# MotorControlV4_0.net
KiCad netlist of a schematic drawn in Altium Designer
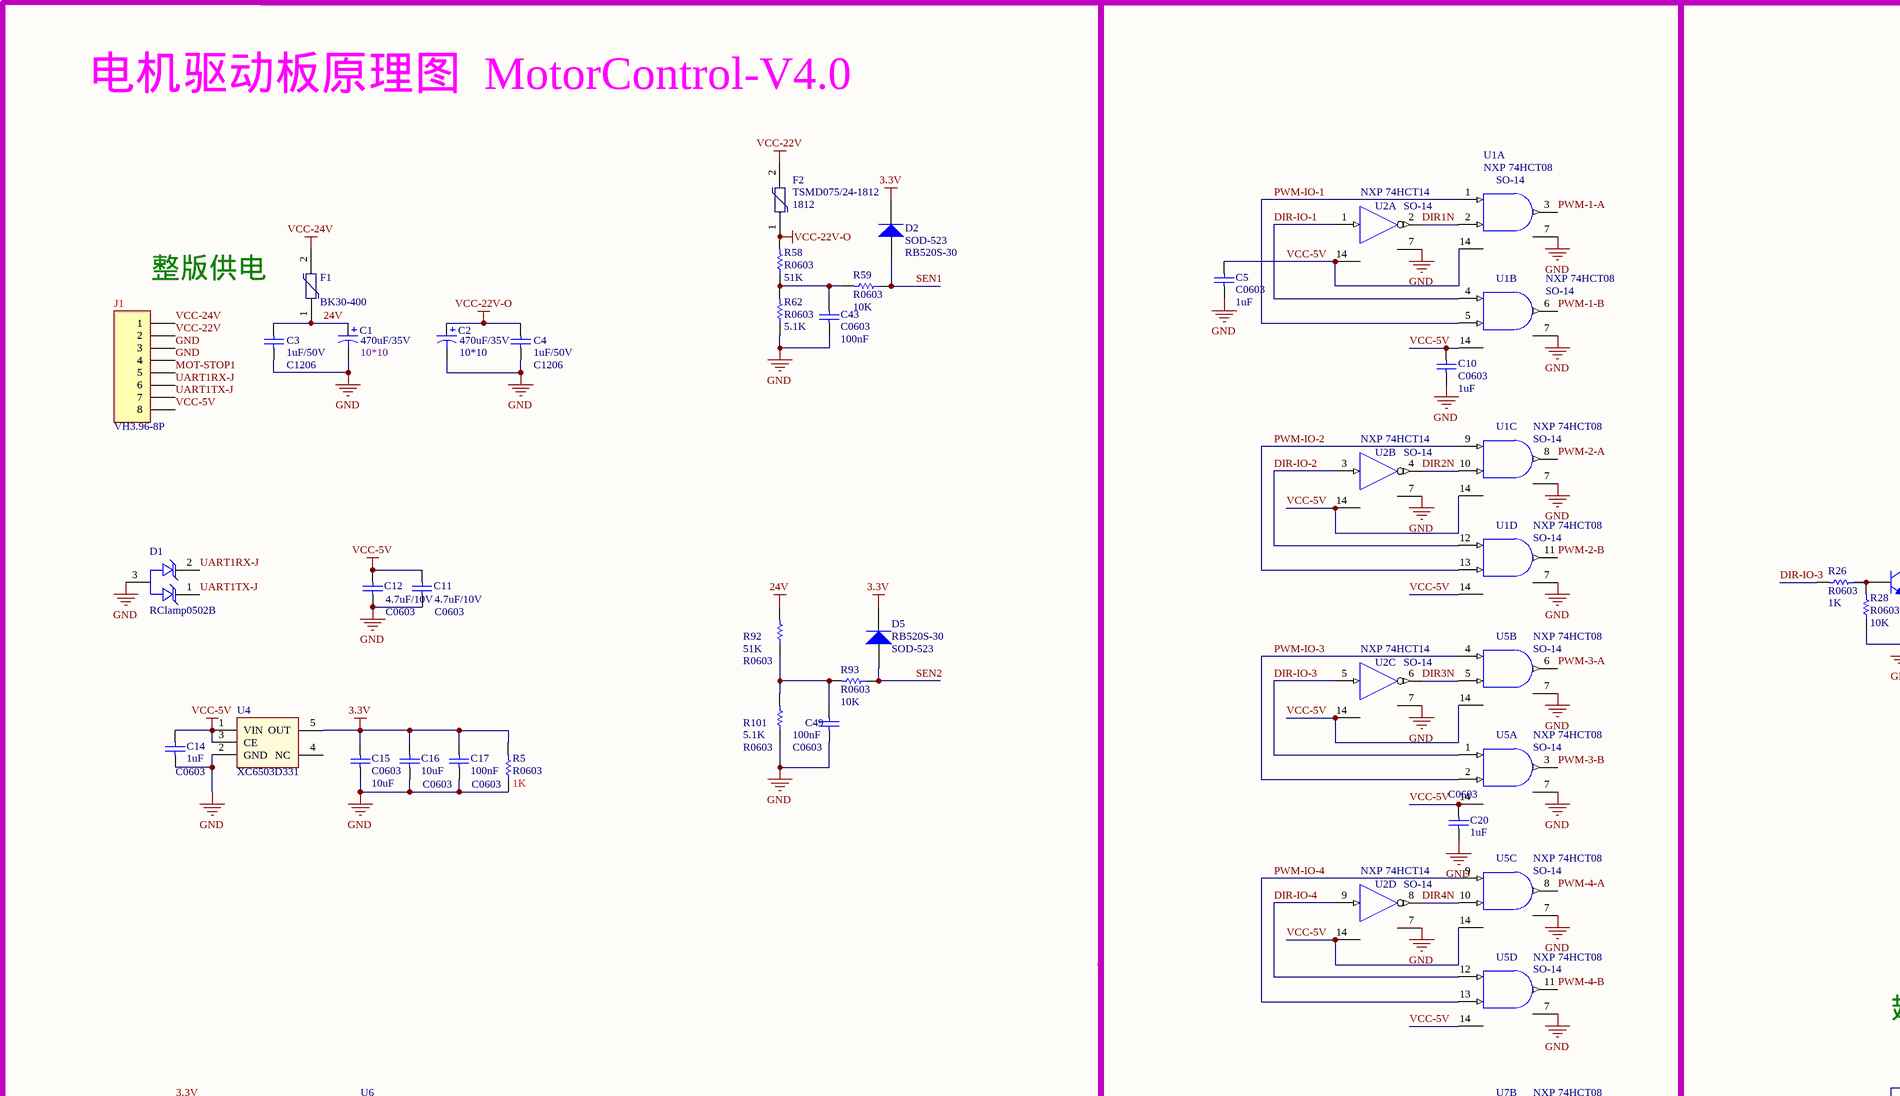
[diagram p0: MotorControlV4.0原理图.SchDoc, top left]
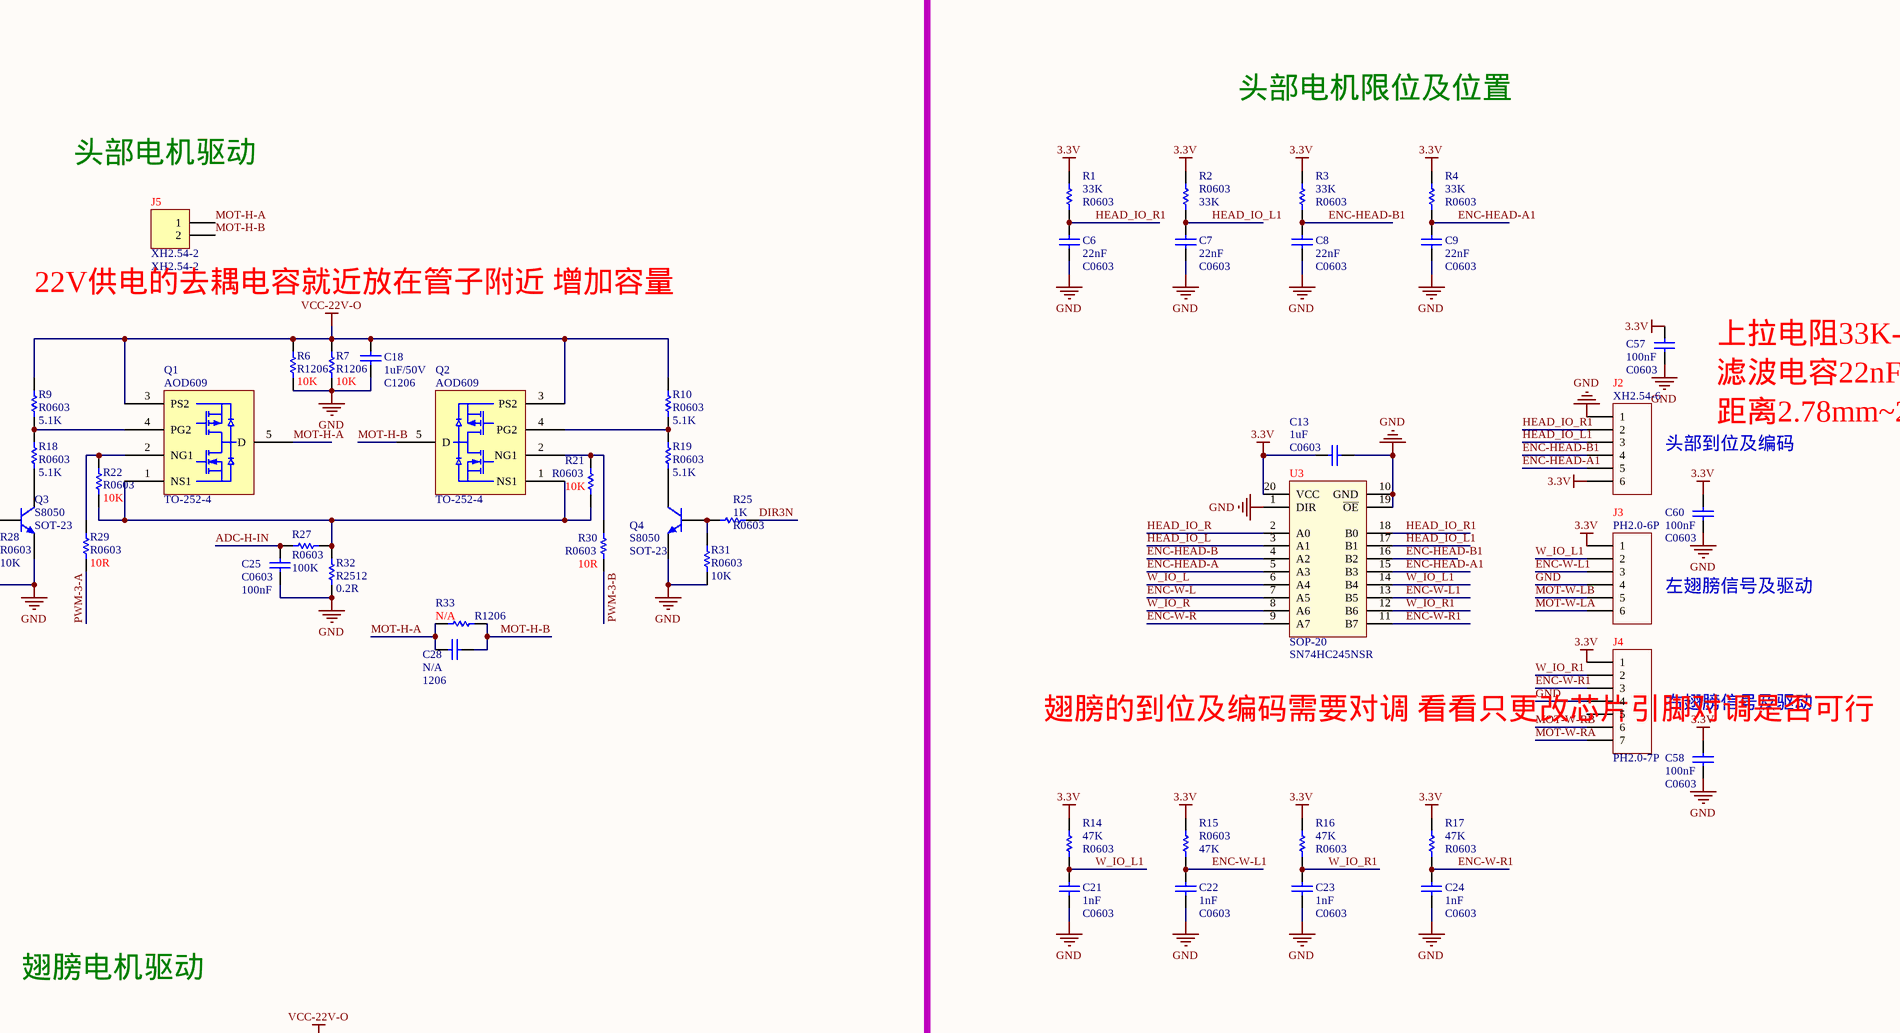
[diagram p1: MotorControlV4.0原理图.SchDoc, top right]
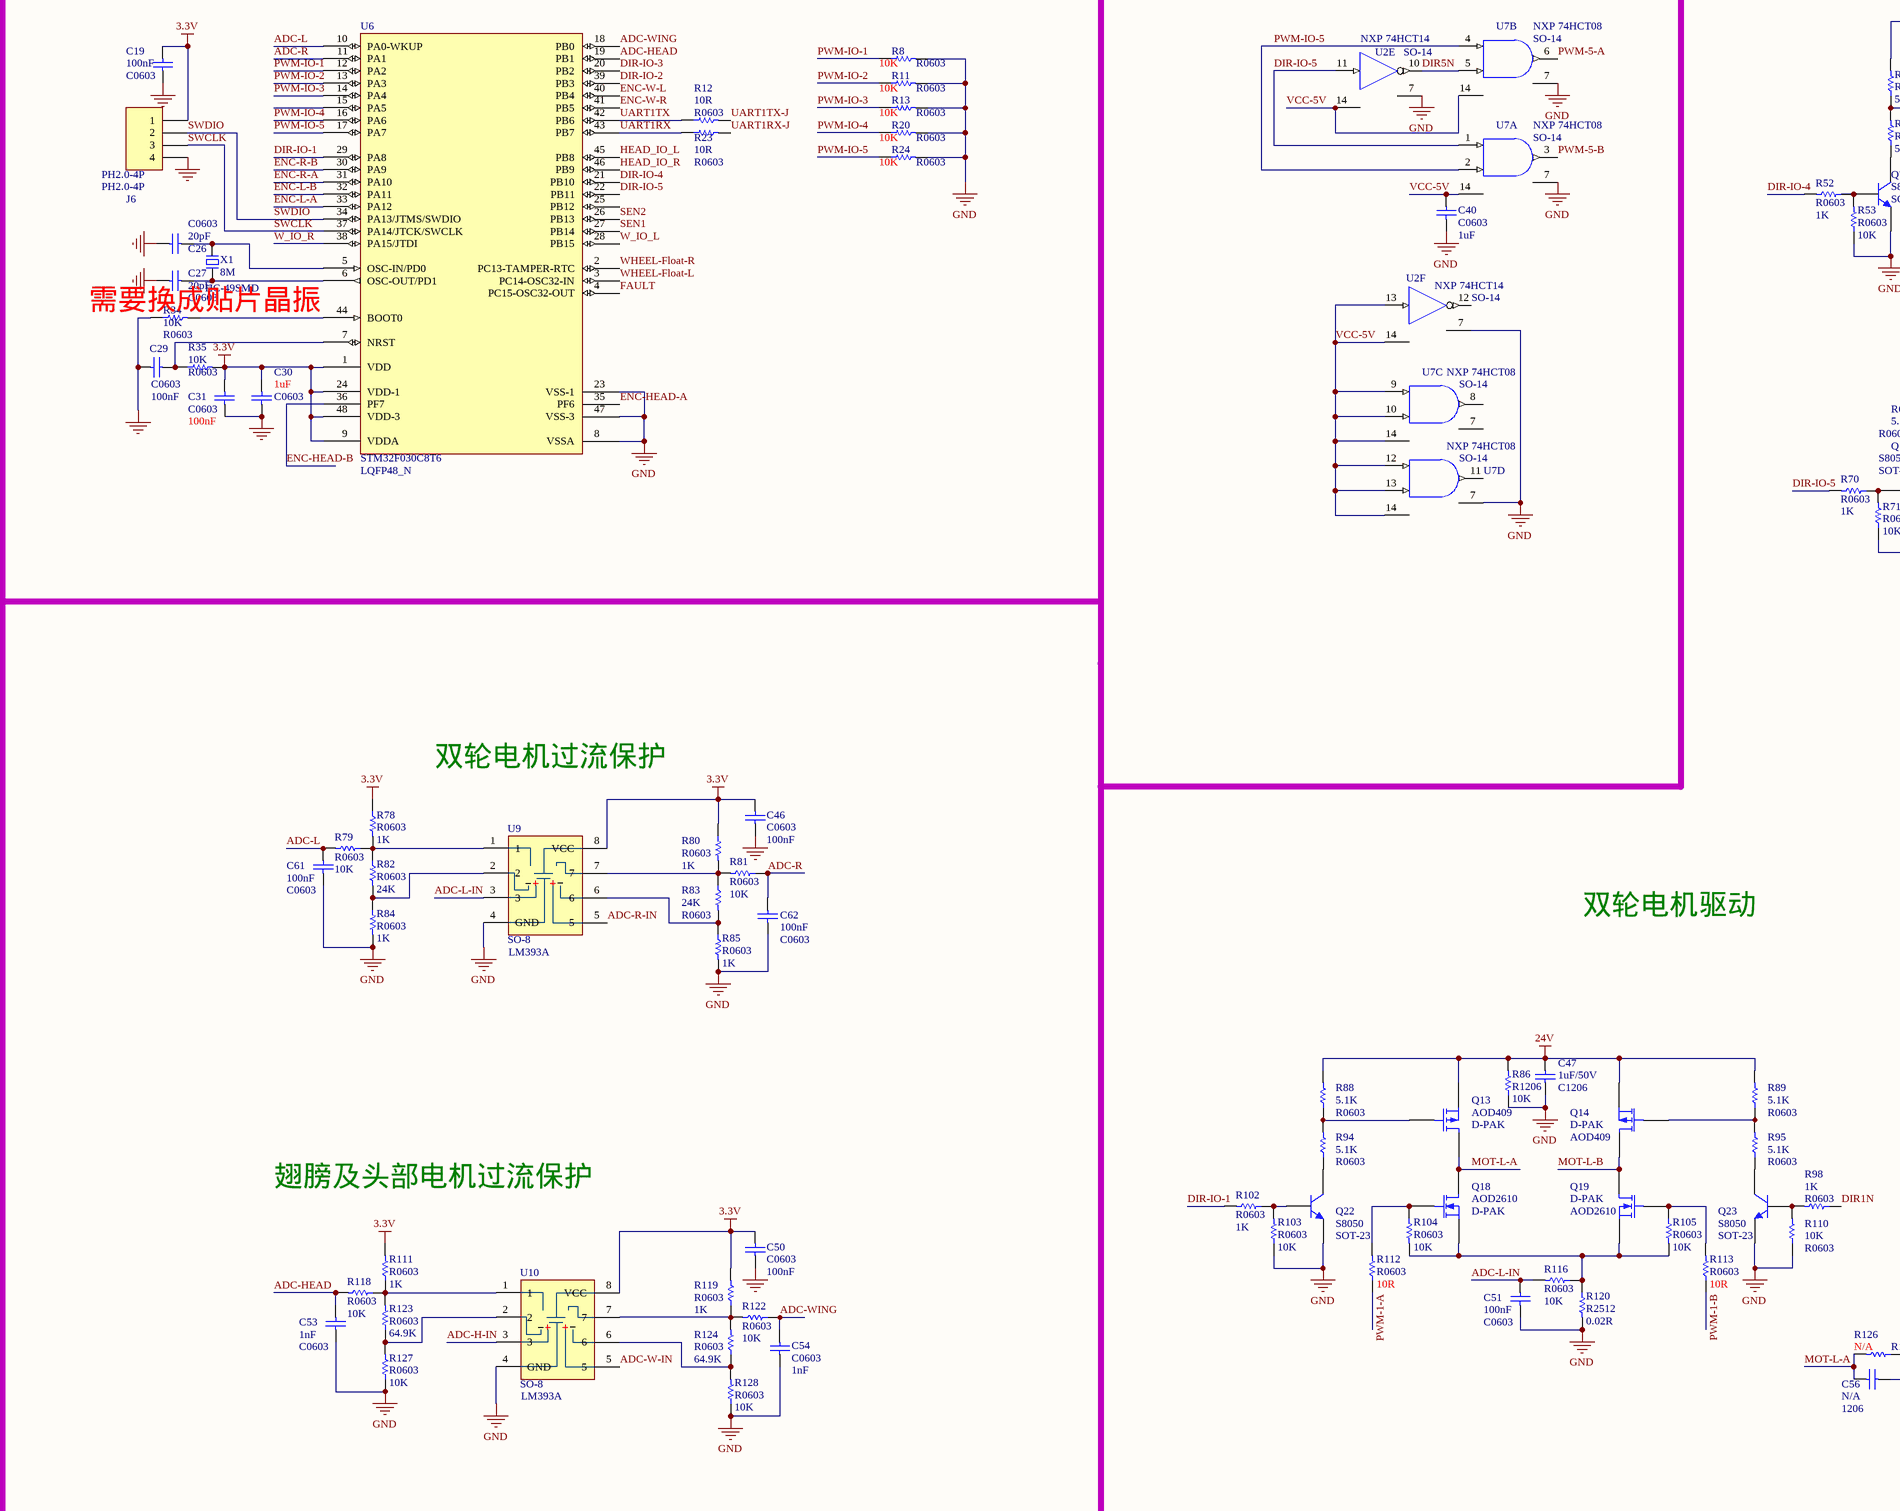
[diagram p2: MotorControlV4.0原理图.SchDoc, bottom left]
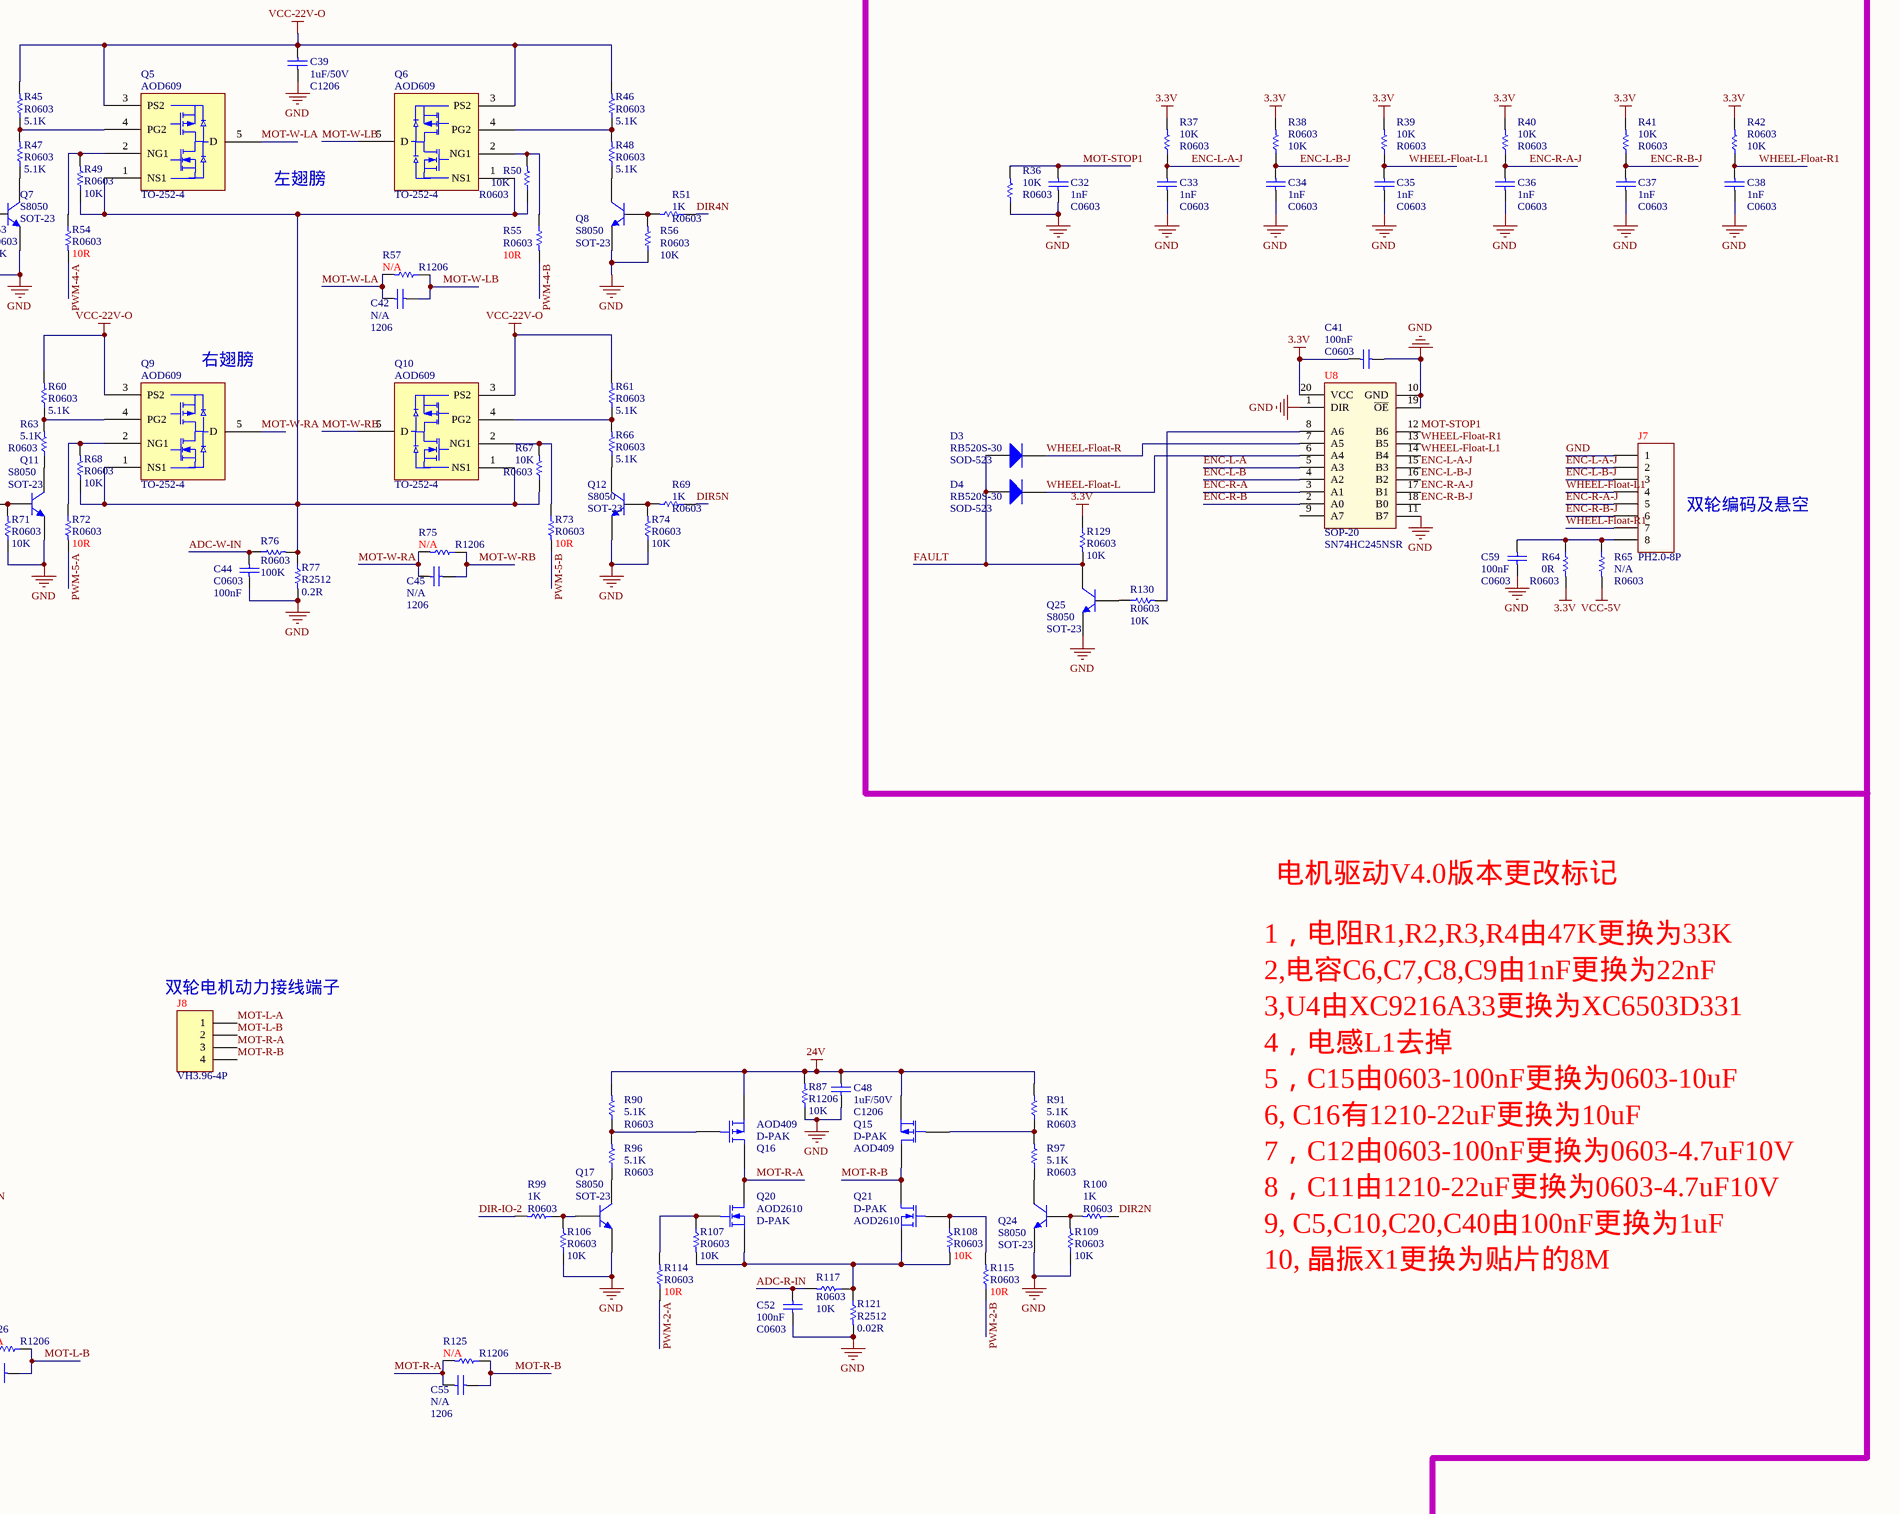
[diagram p3: MotorControlV4.0原理图.SchDoc, bottom right]

(export (version "E")
  (design (tool "Eeschema 10.0.6"))
  (components
    (comp (ref "C1")
      (value "470uF/35V")
      (footprint "CAP_SO_10*10")
      (description "Polarized Capacitor (Surface Mount)")
      (fields (field (name "ALTIUM_VALUE") "10*10") (field (name "PUBLISHER") "Altium Limited"))
      (libsource (lib "Miscellaneous Devices") (part "Cap Pol3"))
    )
    (comp (ref "C2")
      (value "470uF/35V")
      (footprint "CAP_SO_10*10")
      (description "Polarized Capacitor (Surface Mount)")
      (fields (field (name "ALTIUM_VALUE") "10*10") (field (name "PUBLISHER") "Altium Limited"))
      (libsource (lib "Miscellaneous Devices") (part "Cap Pol3"))
    )
    (comp (ref "C3")
      (value "C1206")
      (footprint "1206")
      (description "Capacitor")
      (fields (field (name "ALTIUM_VALUE") "1uF/50V") (field (name "PUBLISHER") "Altium Limited"))
      (libsource (lib "Miscellaneous Devices") (part "Cap"))
    )
    (comp (ref "C4")
      (value "C1206")
      (footprint "1206")
      (description "Capacitor")
      (fields (field (name "ALTIUM_VALUE") "1uF/50V") (field (name "PUBLISHER") "Altium Limited"))
      (libsource (lib "Miscellaneous Devices") (part "Cap"))
    )
    (comp (ref "C5")
      (value "C0603")
      (footprint "C0603_M1608")
      (description "Capacitor")
      (fields (field (name "ALTIUM_VALUE") "1uF") (field (name "PUBLISHER") "Altium Limited"))
      (libsource (lib "Miscellaneous Devices") (part "Cap"))
    )
    (comp (ref "C6")
      (value "C0603")
      (footprint "C0603_M1608")
      (description "Capacitor")
      (fields (field (name "ALTIUM_VALUE") "22nF") (field (name "PUBLISHER") "Altium Limited"))
      (libsource (lib "Miscellaneous Devices") (part "Cap"))
    )
    (comp (ref "C7")
      (value "C0603")
      (footprint "C0603_M1608")
      (description "Capacitor")
      (fields (field (name "ALTIUM_VALUE") "22nF") (field (name "PUBLISHER") "Altium Limited"))
      (libsource (lib "Miscellaneous Devices") (part "Cap"))
    )
    (comp (ref "C8")
      (value "C0603")
      (footprint "C0603_M1608")
      (description "Capacitor")
      (fields (field (name "ALTIUM_VALUE") "22nF") (field (name "PUBLISHER") "Altium Limited"))
      (libsource (lib "Miscellaneous Devices") (part "Cap"))
    )
    (comp (ref "C9")
      (value "C0603")
      (footprint "C0603_M1608")
      (description "Capacitor")
      (fields (field (name "ALTIUM_VALUE") "22nF") (field (name "PUBLISHER") "Altium Limited"))
      (libsource (lib "Miscellaneous Devices") (part "Cap"))
    )
    (comp (ref "C10")
      (value "C0603")
      (footprint "C0603_M1608")
      (description "Capacitor")
      (fields (field (name "ALTIUM_VALUE") "1uF") (field (name "PUBLISHER") "Altium Limited"))
      (libsource (lib "Miscellaneous Devices") (part "Cap"))
    )
    (comp (ref "C11")
      (value "C0603")
      (footprint "C0603_M1608")
      (description "Capacitor")
      (fields (field (name "ALTIUM_VALUE") "4.7uF/10V") (field (name "PUBLISHER") "Altium Limited"))
      (libsource (lib "Miscellaneous Devices") (part "Cap"))
    )
    (comp (ref "C12")
      (value "C0603")
      (footprint "C0603_M1608")
      (description "Capacitor")
      (fields (field (name "ALTIUM_VALUE") "4.7uF/10V") (field (name "PUBLISHER") "Altium Limited"))
      (libsource (lib "Miscellaneous Devices") (part "Cap"))
    )
    (comp (ref "C13")
      (value "C0603")
      (footprint "C0603_M1608")
      (description "Capacitor")
      (fields (field (name "ALTIUM_VALUE") "1uF") (field (name "PUBLISHER") "Altium Limited"))
      (libsource (lib "Miscellaneous Devices") (part "Cap"))
    )
    (comp (ref "C14")
      (value "C0603")
      (footprint "C0603_M1608")
      (description "Capacitor")
      (fields (field (name "ALTIUM_VALUE") "1uF") (field (name "PUBLISHER") "Altium Limited"))
      (libsource (lib "Miscellaneous Devices") (part "Cap"))
    )
    (comp (ref "C15")
      (value "C0603")
      (footprint "C0603_M1608")
      (description "Capacitor")
      (fields (field (name "ALTIUM_VALUE") "10uF") (field (name "PUBLISHER") "Altium Limited"))
      (libsource (lib "Miscellaneous Devices") (part "Cap"))
    )
    (comp (ref "C16")
      (value "C0603")
      (footprint "C0603_M1608")
      (description "Capacitor")
      (fields (field (name "ALTIUM_VALUE") "10uF") (field (name "PUBLISHER") "Altium Limited"))
      (libsource (lib "Miscellaneous Devices") (part "Cap"))
    )
    (comp (ref "C17")
      (value "C0603")
      (footprint "C0603_M1608")
      (description "Capacitor")
      (fields (field (name "ALTIUM_VALUE") "100nF") (field (name "PUBLISHER") "Altium Limited"))
      (libsource (lib "Miscellaneous Devices") (part "Cap"))
    )
    (comp (ref "C18")
      (value "C1206")
      (footprint "1206")
      (description "Capacitor")
      (fields (field (name "ALTIUM_VALUE") "1uF/50V") (field (name "PUBLISHER") "Altium Limited"))
      (libsource (lib "Miscellaneous Devices") (part "Cap"))
    )
    (comp (ref "C19")
      (value "C0603")
      (footprint "C0603_M1608")
      (description "Capacitor")
      (fields (field (name "ALTIUM_VALUE") "100nF") (field (name "PUBLISHER") "Altium Limited"))
      (libsource (lib "Miscellaneous Devices") (part "Cap"))
    )
    (comp (ref "C20")
      (value "C0603")
      (footprint "C0603_M1608")
      (description "Capacitor")
      (fields (field (name "ALTIUM_VALUE") "1uF") (field (name "PUBLISHER") "Altium Limited"))
      (libsource (lib "Miscellaneous Devices") (part "Cap"))
    )
    (comp (ref "C21")
      (value "C0603")
      (footprint "C0603_M1608")
      (description "Capacitor")
      (fields (field (name "ALTIUM_VALUE") "1nF") (field (name "PUBLISHER") "Altium Limited"))
      (libsource (lib "Miscellaneous Devices") (part "Cap"))
    )
    (comp (ref "C22")
      (value "C0603")
      (footprint "C0603_M1608")
      (description "Capacitor")
      (fields (field (name "ALTIUM_VALUE") "1nF") (field (name "PUBLISHER") "Altium Limited"))
      (libsource (lib "Miscellaneous Devices") (part "Cap"))
    )
    (comp (ref "C23")
      (value "C0603")
      (footprint "C0603_M1608")
      (description "Capacitor")
      (fields (field (name "ALTIUM_VALUE") "1nF") (field (name "PUBLISHER") "Altium Limited"))
      (libsource (lib "Miscellaneous Devices") (part "Cap"))
    )
    (comp (ref "C24")
      (value "C0603")
      (footprint "C0603_M1608")
      (description "Capacitor")
      (fields (field (name "ALTIUM_VALUE") "1nF") (field (name "PUBLISHER") "Altium Limited"))
      (libsource (lib "Miscellaneous Devices") (part "Cap"))
    )
    (comp (ref "C25")
      (value "C0603")
      (footprint "C0603_M1608")
      (description "Capacitor")
      (fields (field (name "ALTIUM_VALUE") "100nF") (field (name "PUBLISHER") "Altium Limited"))
      (libsource (lib "Miscellaneous Devices") (part "Cap"))
    )
    (comp (ref "C26")
      (value "C0603")
      (footprint "C0603_M1608")
      (description "Capacitor")
      (fields (field (name "ALTIUM_VALUE") "20pF") (field (name "PUBLISHER") "Altium Limited"))
      (libsource (lib "Miscellaneous Devices") (part "Cap"))
    )
    (comp (ref "C27")
      (value "C0603")
      (footprint "C0603_M1608")
      (description "Capacitor")
      (fields (field (name "ALTIUM_VALUE") "20pF") (field (name "PUBLISHER") "Altium Limited"))
      (libsource (lib "Miscellaneous Devices") (part "Cap"))
    )
    (comp (ref "C28")
      (value "1206")
      (footprint "1206")
      (description "Capacitor")
      (fields (field (name "ALTIUM_VALUE") "N/A") (field (name "PUBLISHER") "Altium Limited"))
      (libsource (lib "Miscellaneous Devices") (part "Cap"))
    )
    (comp (ref "C29")
      (value "C0603")
      (footprint "C0603_M1608")
      (description "Capacitor")
      (fields (field (name "ALTIUM_VALUE") "100nF") (field (name "PUBLISHER") "Altium Limited"))
      (libsource (lib "Miscellaneous Devices") (part "Cap"))
    )
    (comp (ref "C30")
      (value "C0603")
      (footprint "C0603_M1608")
      (description "Capacitor")
      (fields (field (name "ALTIUM_VALUE") "1uF") (field (name "PUBLISHER") "Altium Limited"))
      (libsource (lib "Miscellaneous Devices") (part "Cap"))
    )
    (comp (ref "C31")
      (value "C0603")
      (footprint "C0603_M1608")
      (description "Capacitor")
      (fields (field (name "ALTIUM_VALUE") "100nF") (field (name "PUBLISHER") "Altium Limited"))
      (libsource (lib "Miscellaneous Devices") (part "Cap"))
    )
    (comp (ref "C32")
      (value "C0603")
      (footprint "C0603_M1608")
      (description "Capacitor")
      (fields (field (name "ALTIUM_VALUE") "1nF") (field (name "PUBLISHER") "Altium Limited"))
      (libsource (lib "Miscellaneous Devices") (part "Cap"))
    )
    (comp (ref "C33")
      (value "C0603")
      (footprint "C0603_M1608")
      (description "Capacitor")
      (fields (field (name "ALTIUM_VALUE") "1nF") (field (name "PUBLISHER") "Altium Limited"))
      (libsource (lib "Miscellaneous Devices") (part "Cap"))
    )
    (comp (ref "C34")
      (value "C0603")
      (footprint "C0603_M1608")
      (description "Capacitor")
      (fields (field (name "ALTIUM_VALUE") "1nF") (field (name "PUBLISHER") "Altium Limited"))
      (libsource (lib "Miscellaneous Devices") (part "Cap"))
    )
    (comp (ref "C35")
      (value "C0603")
      (footprint "C0603_M1608")
      (description "Capacitor")
      (fields (field (name "ALTIUM_VALUE") "1nF") (field (name "PUBLISHER") "Altium Limited"))
      (libsource (lib "Miscellaneous Devices") (part "Cap"))
    )
    (comp (ref "C36")
      (value "C0603")
      (footprint "C0603_M1608")
      (description "Capacitor")
      (fields (field (name "ALTIUM_VALUE") "1nF") (field (name "PUBLISHER") "Altium Limited"))
      (libsource (lib "Miscellaneous Devices") (part "Cap"))
    )
    (comp (ref "C37")
      (value "C0603")
      (footprint "C0603_M1608")
      (description "Capacitor")
      (fields (field (name "ALTIUM_VALUE") "1nF") (field (name "PUBLISHER") "Altium Limited"))
      (libsource (lib "Miscellaneous Devices") (part "Cap"))
    )
    (comp (ref "C38")
      (value "C0603")
      (footprint "C0603_M1608")
      (description "Capacitor")
      (fields (field (name "ALTIUM_VALUE") "1nF") (field (name "PUBLISHER") "Altium Limited"))
      (libsource (lib "Miscellaneous Devices") (part "Cap"))
    )
    (comp (ref "C39")
      (value "C1206")
      (footprint "1206")
      (description "Capacitor")
      (fields (field (name "ALTIUM_VALUE") "1uF/50V") (field (name "PUBLISHER") "Altium Limited"))
      (libsource (lib "Miscellaneous Devices") (part "Cap"))
    )
    (comp (ref "C40")
      (value "C0603")
      (footprint "C0603_M1608")
      (description "Capacitor")
      (fields (field (name "ALTIUM_VALUE") "1uF") (field (name "PUBLISHER") "Altium Limited"))
      (libsource (lib "Miscellaneous Devices") (part "Cap"))
    )
    (comp (ref "C41")
      (value "C0603")
      (footprint "C0603_M1608")
      (description "Capacitor")
      (fields (field (name "ALTIUM_VALUE") "100nF") (field (name "PUBLISHER") "Altium Limited"))
      (libsource (lib "Miscellaneous Devices") (part "Cap"))
    )
    (comp (ref "C42")
      (value "1206")
      (footprint "1206")
      (description "Capacitor")
      (fields (field (name "ALTIUM_VALUE") "N/A") (field (name "PUBLISHER") "Altium Limited"))
      (libsource (lib "Miscellaneous Devices") (part "Cap"))
    )
    (comp (ref "C43")
      (value "C0603")
      (footprint "C0603_M1608")
      (description "Capacitor")
      (fields (field (name "ALTIUM_VALUE") "100nF") (field (name "PUBLISHER") "Altium Limited"))
      (libsource (lib "Miscellaneous Devices") (part "Cap"))
    )
    (comp (ref "C44")
      (value "C0603")
      (footprint "C0603_M1608")
      (description "Capacitor")
      (fields (field (name "ALTIUM_VALUE") "100nF") (field (name "PUBLISHER") "Altium Limited"))
      (libsource (lib "Miscellaneous Devices") (part "Cap"))
    )
    (comp (ref "C45")
      (value "1206")
      (footprint "1206")
      (description "Capacitor")
      (fields (field (name "ALTIUM_VALUE") "N/A") (field (name "PUBLISHER") "Altium Limited"))
      (libsource (lib "Miscellaneous Devices") (part "Cap"))
    )
    (comp (ref "C46")
      (value "C0603")
      (footprint "C0603_M1608")
      (description "Capacitor")
      (fields (field (name "ALTIUM_VALUE") "100nF") (field (name "PUBLISHER") "Altium Limited"))
      (libsource (lib "Miscellaneous Devices") (part "Cap"))
    )
    (comp (ref "C47")
      (value "C1206")
      (footprint "1206")
      (description "Capacitor")
      (fields (field (name "ALTIUM_VALUE") "1uF/50V") (field (name "PUBLISHER") "Altium Limited"))
      (libsource (lib "Miscellaneous Devices") (part "Cap"))
    )
    (comp (ref "C48")
      (value "C1206")
      (footprint "1206")
      (description "Capacitor")
      (fields (field (name "ALTIUM_VALUE") "1uF/50V") (field (name "PUBLISHER") "Altium Limited"))
      (libsource (lib "Miscellaneous Devices") (part "Cap"))
    )
    (comp (ref "C49")
      (value "C0603")
      (footprint "C0603_M1608")
      (description "Capacitor")
      (fields (field (name "ALTIUM_VALUE") "100nF") (field (name "PUBLISHER") "Altium Limited"))
      (libsource (lib "Miscellaneous Devices") (part "Cap"))
    )
    (comp (ref "C50")
      (value "C0603")
      (footprint "C0603_M1608")
      (description "Capacitor")
      (fields (field (name "ALTIUM_VALUE") "100nF") (field (name "PUBLISHER") "Altium Limited"))
      (libsource (lib "Miscellaneous Devices") (part "Cap"))
    )
    (comp (ref "C51")
      (value "C0603")
      (footprint "C0603_M1608")
      (description "Capacitor")
      (fields (field (name "ALTIUM_VALUE") "100nF") (field (name "PUBLISHER") "Altium Limited"))
      (libsource (lib "Miscellaneous Devices") (part "Cap"))
    )
    (comp (ref "C52")
      (value "C0603")
      (footprint "C0603_M1608")
      (description "Capacitor")
      (fields (field (name "ALTIUM_VALUE") "100nF") (field (name "PUBLISHER") "Altium Limited"))
      (libsource (lib "Miscellaneous Devices") (part "Cap"))
    )
    (comp (ref "C53")
      (value "C0603")
      (footprint "C0603_M1608")
      (description "Capacitor")
      (fields (field (name "ALTIUM_VALUE") "1nF") (field (name "PUBLISHER") "Altium Limited"))
      (libsource (lib "Miscellaneous Devices") (part "Cap"))
    )
    (comp (ref "C54")
      (value "C0603")
      (footprint "C0603_M1608")
      (description "Capacitor")
      (fields (field (name "ALTIUM_VALUE") "1nF") (field (name "PUBLISHER") "Altium Limited"))
      (libsource (lib "Miscellaneous Devices") (part "Cap"))
    )
    (comp (ref "C55")
      (value "1206")
      (footprint "1206")
      (description "Capacitor")
      (fields (field (name "ALTIUM_VALUE") "N/A") (field (name "PUBLISHER") "Altium Limited"))
      (libsource (lib "Miscellaneous Devices") (part "Cap"))
    )
    (comp (ref "C56")
      (value "1206")
      (footprint "1206")
      (description "Capacitor")
      (fields (field (name "ALTIUM_VALUE") "N/A") (field (name "PUBLISHER") "Altium Limited"))
      (libsource (lib "Miscellaneous Devices") (part "Cap"))
    )
    (comp (ref "C57")
      (value "C0603")
      (footprint "C0603_M1608")
      (description "Capacitor")
      (fields (field (name "ALTIUM_VALUE") "100nF") (field (name "PUBLISHER") "Altium Limited"))
      (libsource (lib "Miscellaneous Devices") (part "Cap"))
    )
    (comp (ref "C58")
      (value "C0603")
      (footprint "C0603_M1608")
      (description "Capacitor")
      (fields (field (name "ALTIUM_VALUE") "100nF") (field (name "PUBLISHER") "Altium Limited"))
      (libsource (lib "Miscellaneous Devices") (part "Cap"))
    )
    (comp (ref "C59")
      (value "C0603")
      (footprint "C0603_M1608")
      (description "Capacitor")
      (fields (field (name "ALTIUM_VALUE") "100nF") (field (name "PUBLISHER") "Altium Limited"))
      (libsource (lib "Miscellaneous Devices") (part "Cap"))
    )
    (comp (ref "C60")
      (value "C0603")
      (footprint "C0603_M1608")
      (description "Capacitor")
      (fields (field (name "ALTIUM_VALUE") "100nF") (field (name "PUBLISHER") "Altium Limited"))
      (libsource (lib "Miscellaneous Devices") (part "Cap"))
    )
    (comp (ref "C61")
      (value "C0603")
      (footprint "C0603_M1608")
      (description "Capacitor")
      (fields (field (name "ALTIUM_VALUE") "100nF") (field (name "PUBLISHER") "Altium Limited"))
      (libsource (lib "Miscellaneous Devices") (part "Cap"))
    )
    (comp (ref "C62")
      (value "C0603")
      (footprint "C0603_M1608")
      (description "Capacitor")
      (fields (field (name "ALTIUM_VALUE") "100nF") (field (name "PUBLISHER") "Altium Limited"))
      (libsource (lib "Miscellaneous Devices") (part "Cap"))
    )
    (comp (ref "D1") (value "RClamp0502B") (footprint "SOT-523") (libsource (lib "SCH") (part "LCTVS")))
    (comp (ref "D2")
      (value "SOD-523")
      (footprint "SOD-523")
      (description "Default Diode")
      (fields (field (name "ALTIUM_VALUE") "RB520S-30") (field (name "PUBLISHER") "Altium Limited"))
      (libsource (lib "SCH") (part "Diode"))
    )
    (comp (ref "D3")
      (value "SOD-523")
      (footprint "SOD-523")
      (description "Default Diode")
      (fields (field (name "ALTIUM_VALUE") "RB520S-30") (field (name "PUBLISHER") "Altium Limited"))
      (libsource (lib "") (part "Diode_1"))
    )
    (comp (ref "D4")
      (value "SOD-523")
      (footprint "SOD-523")
      (description "Default Diode")
      (fields (field (name "ALTIUM_VALUE") "RB520S-30") (field (name "PUBLISHER") "Altium Limited"))
      (libsource (lib "") (part "Diode_1"))
    )
    (comp (ref "D5")
      (value "SOD-523")
      (footprint "SOD-523")
      (description "Default Diode")
      (fields (field (name "ALTIUM_VALUE") "RB520S-30") (field (name "PUBLISHER") "Altium Limited"))
      (libsource (lib "SCH") (part "Diode"))
    )
    (comp (ref "F1") (value "BK30-400") (footprint "FUSE-FRG-5MM") (libsource (lib "SCH") (part "PPTC")))
    (comp (ref "F2")
      (value "1812")
      (footprint "1812")
      (fields (field (name "ALTIUM_VALUE") "TSMD075/24-1812"))
      (libsource (lib "SCH") (part "PPTC"))
    )
    (comp (ref "J1") (value "VH3.96-8P") (footprint "VH3.96-8P") (libsource (lib "SCH") (part "VH3.96-8P")))
    (comp (ref "J2")
      (value "XH2.54-6")
      (footprint "XH2.54-6")
      (description "Header, 6-Pin")
      (fields (field (name "PUBLISHER") "Altium Limited"))
      (libsource (lib "SCH") (part "PH2.0-6P"))
    )
    (comp (ref "J3")
      (value "PH2.0-6P")
      (footprint "PH2.0-6P")
      (description "Header, 6-Pin")
      (fields (field (name "PUBLISHER") "Altium Limited"))
      (libsource (lib "SCH") (part "PH2.0-6P"))
    )
    (comp (ref "J4")
      (value "PH2.0-7P")
      (footprint "PH2.0-7P")
      (description "Header, 7-Pin")
      (fields (field (name "PUBLISHER") "Altium Limited"))
      (libsource (lib "SCH") (part "PH2.0-7P"))
    )
    (comp (ref "J5")
      (value "XH2.54-2")
      (footprint "XH2.54-2")
      (description "Header, 2-Pin")
      (fields (field (name "ALTIUM_VALUE") "XH2.54-2") (field (name "PUBLISHER") "Altium Limited"))
      (libsource (lib "SCH") (part "XH2P"))
    )
    (comp (ref "J6")
      (value "PH2.0-4P")
      (footprint "PH2.0-4P")
      (description "Header, 4-Pin")
      (fields (field (name "ALTIUM_VALUE") "PH2.0-4P") (field (name "PUBLISHER") "Altium Limited"))
      (libsource (lib "Miscellaneous Connectors") (part "Header 4"))
    )
    (comp (ref "J7")
      (value "PH2.0-8P")
      (footprint "PH2.0-8P")
      (description "Header, 6-Pin")
      (fields (field (name "PUBLISHER") "Altium Limited"))
      (libsource (lib "SCH") (part "PH2.0-8P"))
    )
    (comp (ref "J8")
      (value "VH3.96-4P")
      (footprint "VH3.96-4P")
      (description "Header, 3-Pin")
      (fields (field (name "PUBLISHER") "Altium Limited"))
      (libsource (lib "SCH") (part "VH3.96-4P"))
    )
    (comp (ref "Q1")
      (value "TO-252-4")
      (footprint "TO-252-4L")
      (fields (field (name "ALTIUM_VALUE") "AOD609"))
      (libsource (lib "CYSchlib") (part "MOS-DUAL-N/P"))
    )
    (comp (ref "Q2")
      (value "TO-252-4")
      (footprint "TO-252-4L")
      (fields (field (name "ALTIUM_VALUE") "AOD609"))
      (libsource (lib "") (part "MOS-DUAL-N/P_1"))
    )
    (comp (ref "Q3")
      (value "SOT-23")
      (footprint "SOT-23_L")
      (description "NPN Bipolar Transistor")
      (fields (field (name "ALTIUM_VALUE") "S8050") (field (name "PUBLISHER") "Altium Limited"))
      (libsource (lib "CYSchlib") (part "NPN"))
    )
    (comp (ref "Q4")
      (value "SOT-23")
      (footprint "SOT-23_L")
      (description "NPN Bipolar Transistor")
      (fields (field (name "ALTIUM_VALUE") "S8050") (field (name "PUBLISHER") "Altium Limited"))
      (libsource (lib "CYSchlib") (part "NPN"))
    )
    (comp (ref "Q5")
      (value "TO-252-4")
      (footprint "TO-252-4L")
      (fields (field (name "ALTIUM_VALUE") "AOD609"))
      (libsource (lib "CYSchlib") (part "MOS-DUAL-N/P"))
    )
    (comp (ref "Q6")
      (value "TO-252-4")
      (footprint "TO-252-4L")
      (fields (field (name "ALTIUM_VALUE") "AOD609"))
      (libsource (lib "") (part "MOS-DUAL-N/P_1"))
    )
    (comp (ref "Q7")
      (value "SOT-23")
      (footprint "SOT-23_L")
      (description "NPN Bipolar Transistor")
      (fields (field (name "ALTIUM_VALUE") "S8050") (field (name "PUBLISHER") "Altium Limited"))
      (libsource (lib "CYSchlib") (part "NPN"))
    )
    (comp (ref "Q8")
      (value "SOT-23")
      (footprint "SOT-23_L")
      (description "NPN Bipolar Transistor")
      (fields (field (name "ALTIUM_VALUE") "S8050") (field (name "PUBLISHER") "Altium Limited"))
      (libsource (lib "CYSchlib") (part "NPN"))
    )
    (comp (ref "Q9")
      (value "TO-252-4")
      (footprint "TO-252-4L")
      (fields (field (name "ALTIUM_VALUE") "AOD609"))
      (libsource (lib "CYSchlib") (part "MOS-DUAL-N/P"))
    )
    (comp (ref "Q10")
      (value "TO-252-4")
      (footprint "TO-252-4L")
      (fields (field (name "ALTIUM_VALUE") "AOD609"))
      (libsource (lib "") (part "MOS-DUAL-N/P_1"))
    )
    (comp (ref "Q11")
      (value "SOT-23")
      (footprint "SOT-23_L")
      (description "NPN Bipolar Transistor")
      (fields (field (name "ALTIUM_VALUE") "S8050") (field (name "PUBLISHER") "Altium Limited"))
      (libsource (lib "CYSchlib") (part "NPN"))
    )
    (comp (ref "Q12")
      (value "SOT-23")
      (footprint "SOT-23_L")
      (description "NPN Bipolar Transistor")
      (fields (field (name "ALTIUM_VALUE") "S8050") (field (name "PUBLISHER") "Altium Limited"))
      (libsource (lib "CYSchlib") (part "NPN"))
    )
    (comp (ref "Q13")
      (value "D-PAK")
      (footprint "TO-252-2L")
      (description "P-Channel MOSFET")
      (fields (field (name "ALTIUM_VALUE") "AOD409") (field (name "PUBLISHER") "Altium Limited"))
      (libsource (lib "CYSchlib") (part "MOS-P"))
    )
    (comp (ref "Q14")
      (value "D-PAK")
      (footprint "TO-252-2L")
      (description "P-Channel MOSFET")
      (fields (field (name "ALTIUM_VALUE") "AOD409") (field (name "PUBLISHER") "Altium Limited"))
      (libsource (lib "CYSchlib") (part "MOS-P"))
    )
    (comp (ref "Q15")
      (value "D-PAK")
      (footprint "TO-252-2L")
      (description "P-Channel MOSFET")
      (fields (field (name "ALTIUM_VALUE") "AOD409") (field (name "PUBLISHER") "Altium Limited"))
      (libsource (lib "CYSchlib") (part "MOS-P"))
    )
    (comp (ref "Q16")
      (value "D-PAK")
      (footprint "TO-252-2L")
      (description "P-Channel MOSFET")
      (fields (field (name "ALTIUM_VALUE") "AOD409") (field (name "PUBLISHER") "Altium Limited"))
      (libsource (lib "CYSchlib") (part "MOS-P"))
    )
    (comp (ref "Q17")
      (value "SOT-23")
      (footprint "SOT-23_L")
      (description "NPN Bipolar Transistor")
      (fields (field (name "ALTIUM_VALUE") "S8050") (field (name "PUBLISHER") "Altium Limited"))
      (libsource (lib "CYSchlib") (part "NPN"))
    )
    (comp (ref "Q18")
      (value "D-PAK")
      (footprint "TO-252-2L")
      (description "N-Channel MOSFET")
      (fields (field (name "ALTIUM_VALUE") "AOD2610") (field (name "PUBLISHER") "Altium Limited"))
      (libsource (lib "CYSchlib") (part "MOS-N"))
    )
    (comp (ref "Q19")
      (value "D-PAK")
      (footprint "TO-252-2L")
      (description "N-Channel MOSFET")
      (fields (field (name "ALTIUM_VALUE") "AOD2610") (field (name "PUBLISHER") "Altium Limited"))
      (libsource (lib "CYSchlib") (part "MOS-N"))
    )
    (comp (ref "Q20")
      (value "D-PAK")
      (footprint "TO-252-2L")
      (description "N-Channel MOSFET")
      (fields (field (name "ALTIUM_VALUE") "AOD2610") (field (name "PUBLISHER") "Altium Limited"))
      (libsource (lib "CYSchlib") (part "MOS-N"))
    )
    (comp (ref "Q21")
      (value "D-PAK")
      (footprint "TO-252-2L")
      (description "N-Channel MOSFET")
      (fields (field (name "ALTIUM_VALUE") "AOD2610") (field (name "PUBLISHER") "Altium Limited"))
      (libsource (lib "CYSchlib") (part "MOS-N"))
    )
    (comp (ref "Q22")
      (value "SOT-23")
      (footprint "SOT-23_L")
      (description "NPN Bipolar Transistor")
      (fields (field (name "ALTIUM_VALUE") "S8050") (field (name "PUBLISHER") "Altium Limited"))
      (libsource (lib "CYSchlib") (part "NPN"))
    )
    (comp (ref "Q23")
      (value "SOT-23")
      (footprint "SOT-23_L")
      (description "NPN Bipolar Transistor")
      (fields (field (name "ALTIUM_VALUE") "S8050") (field (name "PUBLISHER") "Altium Limited"))
      (libsource (lib "CYSchlib") (part "NPN"))
    )
    (comp (ref "Q24")
      (value "SOT-23")
      (footprint "SOT-23_L")
      (description "NPN Bipolar Transistor")
      (fields (field (name "ALTIUM_VALUE") "S8050") (field (name "PUBLISHER") "Altium Limited"))
      (libsource (lib "CYSchlib") (part "NPN"))
    )
    (comp (ref "Q25")
      (value "SOT-23")
      (footprint "SOT-23_L")
      (description "NPN Bipolar Transistor")
      (fields (field (name "ALTIUM_VALUE") "S8050") (field (name "PUBLISHER") "Altium Limited"))
      (libsource (lib "CYSchlib") (part "NPN"))
    )
    (comp (ref "R1")
      (value "R0603")
      (footprint "0603")
      (description "Resistor")
      (fields (field (name "ALTIUM_VALUE") "33K") (field (name "PUBLISHER") "Altium Limited"))
      (libsource (lib "Miscellaneous Devices") (part "Res1"))
    )
    (comp (ref "R2")
      (value "R0603")
      (footprint "0603")
      (description "Resistor")
      (fields (field (name "ALTIUM_VALUE") "33K") (field (name "PUBLISHER") "Altium Limited"))
      (libsource (lib "Miscellaneous Devices") (part "Res1"))
    )
    (comp (ref "R3")
      (value "R0603")
      (footprint "0603")
      (description "Resistor")
      (fields (field (name "ALTIUM_VALUE") "33K") (field (name "PUBLISHER") "Altium Limited"))
      (libsource (lib "Miscellaneous Devices") (part "Res1"))
    )
    (comp (ref "R4")
      (value "R0603")
      (footprint "0603")
      (description "Resistor")
      (fields (field (name "ALTIUM_VALUE") "33K") (field (name "PUBLISHER") "Altium Limited"))
      (libsource (lib "Miscellaneous Devices") (part "Res1"))
    )
    (comp (ref "R5")
      (value "R0603")
      (footprint "0603")
      (description "Resistor")
      (fields (field (name "ALTIUM_VALUE") "1K") (field (name "PUBLISHER") "Altium Limited"))
      (libsource (lib "Miscellaneous Devices") (part "Res1"))
    )
    (comp (ref "R6")
      (value "R1206")
      (footprint "1206")
      (description "Resistor")
      (fields (field (name "ALTIUM_VALUE") "10K") (field (name "PUBLISHER") "Altium Limited"))
      (libsource (lib "Miscellaneous Devices") (part "Res1"))
    )
    (comp (ref "R7")
      (value "R1206")
      (footprint "1206")
      (description "Resistor")
      (fields (field (name "ALTIUM_VALUE") "10K") (field (name "PUBLISHER") "Altium Limited"))
      (libsource (lib "Miscellaneous Devices") (part "Res1"))
    )
    (comp (ref "R8")
      (value "R0603")
      (footprint "0603")
      (description "Resistor")
      (fields (field (name "ALTIUM_VALUE") "10K") (field (name "PUBLISHER") "Altium Limited"))
      (libsource (lib "Miscellaneous Devices") (part "Res1"))
    )
    (comp (ref "R9")
      (value "R0603")
      (footprint "0603")
      (description "Resistor")
      (fields (field (name "ALTIUM_VALUE") "5.1K") (field (name "PUBLISHER") "Altium Limited"))
      (libsource (lib "Miscellaneous Devices") (part "Res1"))
    )
    (comp (ref "R10")
      (value "R0603")
      (footprint "0603")
      (description "Resistor")
      (fields (field (name "ALTIUM_VALUE") "5.1K") (field (name "PUBLISHER") "Altium Limited"))
      (libsource (lib "Miscellaneous Devices") (part "Res1"))
    )
    (comp (ref "R11")
      (value "R0603")
      (footprint "0603")
      (description "Resistor")
      (fields (field (name "ALTIUM_VALUE") "10K") (field (name "PUBLISHER") "Altium Limited"))
      (libsource (lib "Miscellaneous Devices") (part "Res1"))
    )
    (comp (ref "R12")
      (value "R0603")
      (footprint "0603")
      (description "Resistor")
      (fields (field (name "ALTIUM_VALUE") "10R") (field (name "PUBLISHER") "Altium Limited"))
      (libsource (lib "Miscellaneous Devices") (part "Res1"))
    )
    (comp (ref "R13")
      (value "R0603")
      (footprint "0603")
      (description "Resistor")
      (fields (field (name "ALTIUM_VALUE") "10K") (field (name "PUBLISHER") "Altium Limited"))
      (libsource (lib "Miscellaneous Devices") (part "Res1"))
    )
    (comp (ref "R14")
      (value "R0603")
      (footprint "0603")
      (description "Resistor")
      (fields (field (name "ALTIUM_VALUE") "47K") (field (name "PUBLISHER") "Altium Limited"))
      (libsource (lib "Miscellaneous Devices") (part "Res1"))
    )
    (comp (ref "R15")
      (value "R0603")
      (footprint "0603")
      (description "Resistor")
      (fields (field (name "ALTIUM_VALUE") "47K") (field (name "PUBLISHER") "Altium Limited"))
      (libsource (lib "Miscellaneous Devices") (part "Res1"))
    )
    (comp (ref "R16")
      (value "R0603")
      (footprint "0603")
      (description "Resistor")
      (fields (field (name "ALTIUM_VALUE") "47K") (field (name "PUBLISHER") "Altium Limited"))
      (libsource (lib "Miscellaneous Devices") (part "Res1"))
    )
    (comp (ref "R17")
      (value "R0603")
      (footprint "0603")
      (description "Resistor")
      (fields (field (name "ALTIUM_VALUE") "47K") (field (name "PUBLISHER") "Altium Limited"))
      (libsource (lib "Miscellaneous Devices") (part "Res1"))
    )
    (comp (ref "R18")
      (value "R0603")
      (footprint "0603")
      (description "Resistor")
      (fields (field (name "ALTIUM_VALUE") "5.1K") (field (name "PUBLISHER") "Altium Limited"))
      (libsource (lib "Miscellaneous Devices") (part "Res1"))
    )
    (comp (ref "R19")
      (value "R0603")
      (footprint "0603")
      (description "Resistor")
      (fields (field (name "ALTIUM_VALUE") "5.1K") (field (name "PUBLISHER") "Altium Limited"))
      (libsource (lib "Miscellaneous Devices") (part "Res1"))
    )
    (comp (ref "R20")
      (value "R0603")
      (footprint "0603")
      (description "Resistor")
      (fields (field (name "ALTIUM_VALUE") "10K") (field (name "PUBLISHER") "Altium Limited"))
      (libsource (lib "Miscellaneous Devices") (part "Res1"))
    )
    (comp (ref "R21")
      (value "R0603")
      (footprint "0603")
      (description "Resistor")
      (fields (field (name "ALTIUM_VALUE") "10K") (field (name "PUBLISHER") "Altium Limited"))
      (libsource (lib "Miscellaneous Devices") (part "Res1"))
    )
    (comp (ref "R22")
      (value "R0603")
      (footprint "0603")
      (description "Resistor")
      (fields (field (name "ALTIUM_VALUE") "10K") (field (name "PUBLISHER") "Altium Limited"))
      (libsource (lib "Miscellaneous Devices") (part "Res1"))
    )
    (comp (ref "R23")
      (value "R0603")
      (footprint "0603")
      (description "Resistor")
      (fields (field (name "ALTIUM_VALUE") "10R") (field (name "PUBLISHER") "Altium Limited"))
      (libsource (lib "Miscellaneous Devices") (part "Res1"))
    )
    (comp (ref "R24")
      (value "R0603")
      (footprint "0603")
      (description "Resistor")
      (fields (field (name "ALTIUM_VALUE") "10K") (field (name "PUBLISHER") "Altium Limited"))
      (libsource (lib "Miscellaneous Devices") (part "Res1"))
    )
    (comp (ref "R25")
      (value "R0603")
      (footprint "0603")
      (description "Resistor")
      (fields (field (name "ALTIUM_VALUE") "1K") (field (name "PUBLISHER") "Altium Limited"))
      (libsource (lib "Miscellaneous Devices") (part "Res1"))
    )
    (comp (ref "R26")
      (value "R0603")
      (footprint "0603")
      (description "Resistor")
      (fields (field (name "ALTIUM_VALUE") "1K") (field (name "PUBLISHER") "Altium Limited"))
      (libsource (lib "Miscellaneous Devices") (part "Res1"))
    )
    (comp (ref "R27")
      (value "R0603")
      (footprint "0603")
      (description "Resistor")
      (fields (field (name "ALTIUM_VALUE") "100K") (field (name "PUBLISHER") "Altium Limited"))
      (libsource (lib "Miscellaneous Devices") (part "Res1"))
    )
    (comp (ref "R28")
      (value "R0603")
      (footprint "0603")
      (description "Resistor")
      (fields (field (name "ALTIUM_VALUE") "10K") (field (name "PUBLISHER") "Altium Limited"))
      (libsource (lib "Miscellaneous Devices") (part "Res1"))
    )
    (comp (ref "R29")
      (value "R0603")
      (footprint "0603")
      (description "Resistor")
      (fields (field (name "ALTIUM_VALUE") "10R") (field (name "PUBLISHER") "Altium Limited"))
      (libsource (lib "Miscellaneous Devices") (part "Res1"))
    )
    (comp (ref "R30")
      (value "R0603")
      (footprint "0603")
      (description "Resistor")
      (fields (field (name "ALTIUM_VALUE") "10R") (field (name "PUBLISHER") "Altium Limited"))
      (libsource (lib "Miscellaneous Devices") (part "Res1"))
    )
    (comp (ref "R31")
      (value "R0603")
      (footprint "0603")
      (description "Resistor")
      (fields (field (name "ALTIUM_VALUE") "10K") (field (name "PUBLISHER") "Altium Limited"))
      (libsource (lib "Miscellaneous Devices") (part "Res1"))
    )
    (comp (ref "R32")
      (value "R2512")
      (footprint "R2512")
      (description "Resistor")
      (fields (field (name "ALTIUM_VALUE") "0.2R") (field (name "PUBLISHER") "Altium Limited"))
      (libsource (lib "Miscellaneous Devices") (part "Res1"))
    )
    (comp (ref "R33")
      (value "R1206")
      (footprint "1206")
      (description "Resistor")
      (fields (field (name "ALTIUM_VALUE") "N/A") (field (name "PUBLISHER") "Altium Limited"))
      (libsource (lib "Miscellaneous Devices") (part "Res1"))
    )
    (comp (ref "R34")
      (value "R0603")
      (footprint "0603")
      (description "Resistor")
      (fields (field (name "ALTIUM_VALUE") "10K") (field (name "PUBLISHER") "Altium Limited"))
      (libsource (lib "Miscellaneous Devices") (part "Res1"))
    )
    (comp (ref "R35")
      (value "R0603")
      (footprint "0603")
      (description "Resistor")
      (fields (field (name "ALTIUM_VALUE") "10K") (field (name "PUBLISHER") "Altium Limited"))
      (libsource (lib "Miscellaneous Devices") (part "Res1"))
    )
    (comp (ref "R36")
      (value "R0603")
      (footprint "0603")
      (description "Resistor")
      (fields (field (name "ALTIUM_VALUE") "10K") (field (name "PUBLISHER") "Altium Limited"))
      (libsource (lib "Miscellaneous Devices") (part "Res1"))
    )
    (comp (ref "R37")
      (value "R0603")
      (footprint "0603")
      (description "Resistor")
      (fields (field (name "ALTIUM_VALUE") "10K") (field (name "PUBLISHER") "Altium Limited"))
      (libsource (lib "Miscellaneous Devices") (part "Res1"))
    )
    (comp (ref "R38")
      (value "R0603")
      (footprint "0603")
      (description "Resistor")
      (fields (field (name "ALTIUM_VALUE") "10K") (field (name "PUBLISHER") "Altium Limited"))
      (libsource (lib "Miscellaneous Devices") (part "Res1"))
    )
    (comp (ref "R39")
      (value "R0603")
      (footprint "0603")
      (description "Resistor")
      (fields (field (name "ALTIUM_VALUE") "10K") (field (name "PUBLISHER") "Altium Limited"))
      (libsource (lib "Miscellaneous Devices") (part "Res1"))
    )
    (comp (ref "R40")
      (value "R0603")
      (footprint "0603")
      (description "Resistor")
      (fields (field (name "ALTIUM_VALUE") "10K") (field (name "PUBLISHER") "Altium Limited"))
      (libsource (lib "Miscellaneous Devices") (part "Res1"))
    )
    (comp (ref "R41")
      (value "R0603")
      (footprint "0603")
      (description "Resistor")
      (fields (field (name "ALTIUM_VALUE") "10K") (field (name "PUBLISHER") "Altium Limited"))
      (libsource (lib "Miscellaneous Devices") (part "Res1"))
    )
    (comp (ref "R42")
      (value "R0603")
      (footprint "0603")
      (description "Resistor")
      (fields (field (name "ALTIUM_VALUE") "10K") (field (name "PUBLISHER") "Altium Limited"))
      (libsource (lib "Miscellaneous Devices") (part "Res1"))
    )
    (comp (ref "R45")
      (value "R0603")
      (footprint "0603")
      (description "Resistor")
      (fields (field (name "ALTIUM_VALUE") "5.1K") (field (name "PUBLISHER") "Altium Limited"))
      (libsource (lib "Miscellaneous Devices") (part "Res1"))
    )
    (comp (ref "R46")
      (value "R0603")
      (footprint "0603")
      (description "Resistor")
      (fields (field (name "ALTIUM_VALUE") "5.1K") (field (name "PUBLISHER") "Altium Limited"))
      (libsource (lib "Miscellaneous Devices") (part "Res1"))
    )
    (comp (ref "R47")
      (value "R0603")
      (footprint "0603")
      (description "Resistor")
      (fields (field (name "ALTIUM_VALUE") "5.1K") (field (name "PUBLISHER") "Altium Limited"))
      (libsource (lib "Miscellaneous Devices") (part "Res1"))
    )
    (comp (ref "R48")
      (value "R0603")
      (footprint "0603")
      (description "Resistor")
      (fields (field (name "ALTIUM_VALUE") "5.1K") (field (name "PUBLISHER") "Altium Limited"))
      (libsource (lib "Miscellaneous Devices") (part "Res1"))
    )
    (comp (ref "R49")
      (value "R0603")
      (footprint "0603")
      (description "Resistor")
      (fields (field (name "ALTIUM_VALUE") "10K") (field (name "PUBLISHER") "Altium Limited"))
      (libsource (lib "Miscellaneous Devices") (part "Res1"))
    )
    (comp (ref "R50")
      (value "R0603")
      (footprint "0603")
      (description "Resistor")
      (fields (field (name "ALTIUM_VALUE") "10K") (field (name "PUBLISHER") "Altium Limited"))
      (libsource (lib "Miscellaneous Devices") (part "Res1"))
    )
    (comp (ref "R51")
      (value "R0603")
      (footprint "0603")
      (description "Resistor")
      (fields (field (name "ALTIUM_VALUE") "1K") (field (name "PUBLISHER") "Altium Limited"))
      (libsource (lib "Miscellaneous Devices") (part "Res1"))
    )
    (comp (ref "R52")
      (value "R0603")
      (footprint "0603")
      (description "Resistor")
      (fields (field (name "ALTIUM_VALUE") "1K") (field (name "PUBLISHER") "Altium Limited"))
      (libsource (lib "Miscellaneous Devices") (part "Res1"))
    )
    (comp (ref "R53")
      (value "R0603")
      (footprint "0603")
      (description "Resistor")
      (fields (field (name "ALTIUM_VALUE") "10K") (field (name "PUBLISHER") "Altium Limited"))
      (libsource (lib "Miscellaneous Devices") (part "Res1"))
    )
    (comp (ref "R54")
      (value "R0603")
      (footprint "0603")
      (description "Resistor")
      (fields (field (name "ALTIUM_VALUE") "10R") (field (name "PUBLISHER") "Altium Limited"))
      (libsource (lib "Miscellaneous Devices") (part "Res1"))
    )
    (comp (ref "R55")
      (value "R0603")
      (footprint "0603")
      (description "Resistor")
      (fields (field (name "ALTIUM_VALUE") "10R") (field (name "PUBLISHER") "Altium Limited"))
      (libsource (lib "Miscellaneous Devices") (part "Res1"))
    )
    (comp (ref "R56")
      (value "R0603")
      (footprint "0603")
      (description "Resistor")
      (fields (field (name "ALTIUM_VALUE") "10K") (field (name "PUBLISHER") "Altium Limited"))
      (libsource (lib "Miscellaneous Devices") (part "Res1"))
    )
    (comp (ref "R57")
      (value "R1206")
      (footprint "1206")
      (description "Resistor")
      (fields (field (name "ALTIUM_VALUE") "N/A") (field (name "PUBLISHER") "Altium Limited"))
      (libsource (lib "Miscellaneous Devices") (part "Res1"))
    )
    (comp (ref "R58")
      (value "R0603")
      (footprint "0603")
      (description "Resistor")
      (fields (field (name "ALTIUM_VALUE") "51K") (field (name "PUBLISHER") "Altium Limited"))
      (libsource (lib "Miscellaneous Devices") (part "Res1"))
    )
    (comp (ref "R59")
      (value "R0603")
      (footprint "0603")
      (description "Resistor")
      (fields (field (name "ALTIUM_VALUE") "10K") (field (name "PUBLISHER") "Altium Limited"))
      (libsource (lib "Miscellaneous Devices") (part "Res1"))
    )
    (comp (ref "R60")
      (value "R0603")
      (footprint "0603")
      (description "Resistor")
      (fields (field (name "ALTIUM_VALUE") "5.1K") (field (name "PUBLISHER") "Altium Limited"))
      (libsource (lib "Miscellaneous Devices") (part "Res1"))
    )
    (comp (ref "R61")
      (value "R0603")
      (footprint "0603")
      (description "Resistor")
      (fields (field (name "ALTIUM_VALUE") "5.1K") (field (name "PUBLISHER") "Altium Limited"))
      (libsource (lib "Miscellaneous Devices") (part "Res1"))
    )
    (comp (ref "R62")
      (value "R0603")
      (footprint "0603")
      (description "Resistor")
      (fields (field (name "ALTIUM_VALUE") "5.1K") (field (name "PUBLISHER") "Altium Limited"))
      (libsource (lib "Miscellaneous Devices") (part "Res1"))
    )
    (comp (ref "R63")
      (value "R0603")
      (footprint "0603")
      (description "Resistor")
      (fields (field (name "ALTIUM_VALUE") "5.1K") (field (name "PUBLISHER") "Altium Limited"))
      (libsource (lib "Miscellaneous Devices") (part "Res1"))
    )
    (comp (ref "R64")
      (value "R0603")
      (footprint "0603")
      (description "Resistor")
      (fields (field (name "ALTIUM_VALUE") "0R") (field (name "PUBLISHER") "Altium Limited"))
      (libsource (lib "Miscellaneous Devices") (part "Res1"))
    )
    (comp (ref "R65")
      (value "R0603")
      (footprint "0603")
      (description "Resistor")
      (fields (field (name "ALTIUM_VALUE") "N/A") (field (name "PUBLISHER") "Altium Limited"))
      (libsource (lib "Miscellaneous Devices") (part "Res1"))
    )
    (comp (ref "R66")
      (value "R0603")
      (footprint "0603")
      (description "Resistor")
      (fields (field (name "ALTIUM_VALUE") "5.1K") (field (name "PUBLISHER") "Altium Limited"))
      (libsource (lib "Miscellaneous Devices") (part "Res1"))
    )
    (comp (ref "R67")
      (value "R0603")
      (footprint "0603")
      (description "Resistor")
      (fields (field (name "ALTIUM_VALUE") "10K") (field (name "PUBLISHER") "Altium Limited"))
      (libsource (lib "Miscellaneous Devices") (part "Res1"))
    )
    (comp (ref "R68")
      (value "R0603")
      (footprint "0603")
      (description "Resistor")
      (fields (field (name "ALTIUM_VALUE") "10K") (field (name "PUBLISHER") "Altium Limited"))
      (libsource (lib "Miscellaneous Devices") (part "Res1"))
    )
    (comp (ref "R69")
      (value "R0603")
      (footprint "0603")
      (description "Resistor")
      (fields (field (name "ALTIUM_VALUE") "1K") (field (name "PUBLISHER") "Altium Limited"))
      (libsource (lib "Miscellaneous Devices") (part "Res1"))
    )
    (comp (ref "R70")
      (value "R0603")
      (footprint "0603")
      (description "Resistor")
      (fields (field (name "ALTIUM_VALUE") "1K") (field (name "PUBLISHER") "Altium Limited"))
      (libsource (lib "Miscellaneous Devices") (part "Res1"))
    )
    (comp (ref "R71")
      (value "R0603")
      (footprint "0603")
      (description "Resistor")
      (fields (field (name "ALTIUM_VALUE") "10K") (field (name "PUBLISHER") "Altium Limited"))
      (libsource (lib "Miscellaneous Devices") (part "Res1"))
    )
    (comp (ref "R72")
      (value "R0603")
      (footprint "0603")
      (description "Resistor")
      (fields (field (name "ALTIUM_VALUE") "10R") (field (name "PUBLISHER") "Altium Limited"))
      (libsource (lib "Miscellaneous Devices") (part "Res1"))
    )
    (comp (ref "R73")
      (value "R0603")
      (footprint "0603")
      (description "Resistor")
      (fields (field (name "ALTIUM_VALUE") "10R") (field (name "PUBLISHER") "Altium Limited"))
      (libsource (lib "Miscellaneous Devices") (part "Res1"))
    )
    (comp (ref "R74")
      (value "R0603")
      (footprint "0603")
      (description "Resistor")
      (fields (field (name "ALTIUM_VALUE") "10K") (field (name "PUBLISHER") "Altium Limited"))
      (libsource (lib "Miscellaneous Devices") (part "Res1"))
    )
    (comp (ref "R75")
      (value "R1206")
      (footprint "1206")
      (description "Resistor")
      (fields (field (name "ALTIUM_VALUE") "N/A") (field (name "PUBLISHER") "Altium Limited"))
      (libsource (lib "Miscellaneous Devices") (part "Res1"))
    )
    (comp (ref "R76")
      (value "R0603")
      (footprint "0603")
      (description "Resistor")
      (fields (field (name "ALTIUM_VALUE") "100K") (field (name "PUBLISHER") "Altium Limited"))
      (libsource (lib "Miscellaneous Devices") (part "Res1"))
    )
    (comp (ref "R77")
      (value "R2512")
      (footprint "R2512")
      (description "Resistor")
      (fields (field (name "ALTIUM_VALUE") "0.2R") (field (name "PUBLISHER") "Altium Limited"))
      (libsource (lib "Miscellaneous Devices") (part "Res1"))
    )
    (comp (ref "R78")
      (value "R0603")
      (footprint "0603")
      (description "Resistor")
      (fields (field (name "ALTIUM_VALUE") "1K") (field (name "PUBLISHER") "Altium Limited"))
      (libsource (lib "Miscellaneous Devices") (part "Res1"))
    )
    (comp (ref "R79")
      (value "R0603")
      (footprint "0603")
      (description "Resistor")
      (fields (field (name "ALTIUM_VALUE") "10K") (field (name "PUBLISHER") "Altium Limited"))
      (libsource (lib "Miscellaneous Devices") (part "Res1"))
    )
    (comp (ref "R80")
      (value "R0603")
      (footprint "0603")
      (description "Resistor")
      (fields (field (name "ALTIUM_VALUE") "1K") (field (name "PUBLISHER") "Altium Limited"))
      (libsource (lib "Miscellaneous Devices") (part "Res1"))
    )
    (comp (ref "R81")
      (value "R0603")
      (footprint "0603")
      (description "Resistor")
      (fields (field (name "ALTIUM_VALUE") "10K") (field (name "PUBLISHER") "Altium Limited"))
      (libsource (lib "Miscellaneous Devices") (part "Res1"))
    )
    (comp (ref "R82")
      (value "R0603")
      (footprint "0603")
      (description "Resistor")
      (fields (field (name "ALTIUM_VALUE") "24K") (field (name "PUBLISHER") "Altium Limited"))
      (libsource (lib "Miscellaneous Devices") (part "Res1"))
    )
    (comp (ref "R83")
      (value "R0603")
      (footprint "0603")
      (description "Resistor")
      (fields (field (name "ALTIUM_VALUE") "24K") (field (name "PUBLISHER") "Altium Limited"))
      (libsource (lib "Miscellaneous Devices") (part "Res1"))
    )
    (comp (ref "R84")
      (value "R0603")
      (footprint "0603")
      (description "Resistor")
      (fields (field (name "ALTIUM_VALUE") "1K") (field (name "PUBLISHER") "Altium Limited"))
      (libsource (lib "Miscellaneous Devices") (part "Res1"))
    )
    (comp (ref "R85")
      (value "R0603")
      (footprint "0603")
      (description "Resistor")
      (fields (field (name "ALTIUM_VALUE") "1K") (field (name "PUBLISHER") "Altium Limited"))
      (libsource (lib "Miscellaneous Devices") (part "Res1"))
    )
    (comp (ref "R86")
      (value "R1206")
      (footprint "1206")
      (description "Resistor")
      (fields (field (name "ALTIUM_VALUE") "10K") (field (name "PUBLISHER") "Altium Limited"))
      (libsource (lib "Miscellaneous Devices") (part "Res1"))
    )
    (comp (ref "R87")
      (value "R1206")
      (footprint "1206")
      (description "Resistor")
      (fields (field (name "ALTIUM_VALUE") "10K") (field (name "PUBLISHER") "Altium Limited"))
      (libsource (lib "Miscellaneous Devices") (part "Res1"))
    )
    (comp (ref "R88")
      (value "R0603")
      (footprint "0603")
      (description "Resistor")
      (fields (field (name "ALTIUM_VALUE") "5.1K") (field (name "PUBLISHER") "Altium Limited"))
      (libsource (lib "Miscellaneous Devices") (part "Res1"))
    )
    (comp (ref "R89")
      (value "R0603")
      (footprint "0603")
      (description "Resistor")
      (fields (field (name "ALTIUM_VALUE") "5.1K") (field (name "PUBLISHER") "Altium Limited"))
      (libsource (lib "Miscellaneous Devices") (part "Res1"))
    )
    (comp (ref "R90")
      (value "R0603")
      (footprint "0603")
      (description "Resistor")
      (fields (field (name "ALTIUM_VALUE") "5.1K") (field (name "PUBLISHER") "Altium Limited"))
      (libsource (lib "Miscellaneous Devices") (part "Res1"))
    )
    (comp (ref "R91")
      (value "R0603")
      (footprint "0603")
      (description "Resistor")
      (fields (field (name "ALTIUM_VALUE") "5.1K") (field (name "PUBLISHER") "Altium Limited"))
      (libsource (lib "Miscellaneous Devices") (part "Res1"))
    )
    (comp (ref "R92")
      (value "R0603")
      (footprint "0603")
      (description "Resistor")
      (fields (field (name "ALTIUM_VALUE") "51K") (field (name "PUBLISHER") "Altium Limited"))
      (libsource (lib "Miscellaneous Devices") (part "Res1"))
    )
    (comp (ref "R93")
      (value "R0603")
      (footprint "0603")
      (description "Resistor")
      (fields (field (name "ALTIUM_VALUE") "10K") (field (name "PUBLISHER") "Altium Limited"))
      (libsource (lib "Miscellaneous Devices") (part "Res1"))
    )
    (comp (ref "R94")
      (value "R0603")
      (footprint "0603")
      (description "Resistor")
      (fields (field (name "ALTIUM_VALUE") "5.1K") (field (name "PUBLISHER") "Altium Limited"))
      (libsource (lib "Miscellaneous Devices") (part "Res1"))
    )
    (comp (ref "R95")
      (value "R0603")
      (footprint "0603")
      (description "Resistor")
      (fields (field (name "ALTIUM_VALUE") "5.1K") (field (name "PUBLISHER") "Altium Limited"))
      (libsource (lib "Miscellaneous Devices") (part "Res1"))
    )
    (comp (ref "R96")
      (value "R0603")
      (footprint "0603")
      (description "Resistor")
      (fields (field (name "ALTIUM_VALUE") "5.1K") (field (name "PUBLISHER") "Altium Limited"))
      (libsource (lib "Miscellaneous Devices") (part "Res1"))
    )
    (comp (ref "R97")
      (value "R0603")
      (footprint "0603")
      (description "Resistor")
      (fields (field (name "ALTIUM_VALUE") "5.1K") (field (name "PUBLISHER") "Altium Limited"))
      (libsource (lib "Miscellaneous Devices") (part "Res1"))
    )
    (comp (ref "R98")
      (value "R0603")
      (footprint "0603")
      (description "Resistor")
      (fields (field (name "ALTIUM_VALUE") "1K") (field (name "PUBLISHER") "Altium Limited"))
      (libsource (lib "Miscellaneous Devices") (part "Res1"))
    )
    (comp (ref "R99")
      (value "R0603")
      (footprint "0603")
      (description "Resistor")
      (fields (field (name "ALTIUM_VALUE") "1K") (field (name "PUBLISHER") "Altium Limited"))
      (libsource (lib "Miscellaneous Devices") (part "Res1"))
    )
    (comp (ref "R100")
      (value "R0603")
      (footprint "0603")
      (description "Resistor")
      (fields (field (name "ALTIUM_VALUE") "1K") (field (name "PUBLISHER") "Altium Limited"))
      (libsource (lib "Miscellaneous Devices") (part "Res1"))
    )
    (comp (ref "R101")
      (value "R0603")
      (footprint "0603")
      (description "Resistor")
      (fields (field (name "ALTIUM_VALUE") "5.1K") (field (name "PUBLISHER") "Altium Limited"))
      (libsource (lib "Miscellaneous Devices") (part "Res1"))
    )
    (comp (ref "R102")
      (value "R0603")
      (footprint "0603")
      (description "Resistor")
      (fields (field (name "ALTIUM_VALUE") "1K") (field (name "PUBLISHER") "Altium Limited"))
      (libsource (lib "Miscellaneous Devices") (part "Res1"))
    )
    (comp (ref "R103")
      (value "R0603")
      (footprint "0603")
      (description "Resistor")
      (fields (field (name "ALTIUM_VALUE") "10K") (field (name "PUBLISHER") "Altium Limited"))
      (libsource (lib "Miscellaneous Devices") (part "Res1"))
    )
    (comp (ref "R104")
      (value "R0603")
      (footprint "0603")
      (description "Resistor")
      (fields (field (name "ALTIUM_VALUE") "10K") (field (name "PUBLISHER") "Altium Limited"))
      (libsource (lib "Miscellaneous Devices") (part "Res1"))
    )
    (comp (ref "R105")
      (value "R0603")
      (footprint "0603")
      (description "Resistor")
      (fields (field (name "ALTIUM_VALUE") "10K") (field (name "PUBLISHER") "Altium Limited"))
      (libsource (lib "Miscellaneous Devices") (part "Res1"))
    )
    (comp (ref "R106")
      (value "R0603")
      (footprint "0603")
      (description "Resistor")
      (fields (field (name "ALTIUM_VALUE") "10K") (field (name "PUBLISHER") "Altium Limited"))
      (libsource (lib "Miscellaneous Devices") (part "Res1"))
    )
    (comp (ref "R107")
      (value "R0603")
      (footprint "0603")
      (description "Resistor")
      (fields (field (name "ALTIUM_VALUE") "10K") (field (name "PUBLISHER") "Altium Limited"))
      (libsource (lib "Miscellaneous Devices") (part "Res1"))
    )
    (comp (ref "R108")
      (value "R0603")
      (footprint "0603")
      (description "Resistor")
      (fields (field (name "ALTIUM_VALUE") "10K") (field (name "PUBLISHER") "Altium Limited"))
      (libsource (lib "Miscellaneous Devices") (part "Res1"))
    )
    (comp (ref "R109")
      (value "R0603")
      (footprint "0603")
      (description "Resistor")
      (fields (field (name "ALTIUM_VALUE") "10K") (field (name "PUBLISHER") "Altium Limited"))
      (libsource (lib "Miscellaneous Devices") (part "Res1"))
    )
    (comp (ref "R110")
      (value "R0603")
      (footprint "0603")
      (description "Resistor")
      (fields (field (name "ALTIUM_VALUE") "10K") (field (name "PUBLISHER") "Altium Limited"))
      (libsource (lib "Miscellaneous Devices") (part "Res1"))
    )
    (comp (ref "R111")
      (value "R0603")
      (footprint "0603")
      (description "Resistor")
      (fields (field (name "ALTIUM_VALUE") "1K") (field (name "PUBLISHER") "Altium Limited"))
      (libsource (lib "Miscellaneous Devices") (part "Res1"))
    )
    (comp (ref "R112")
      (value "R0603")
      (footprint "0603")
      (description "Resistor")
      (fields (field (name "ALTIUM_VALUE") "10R") (field (name "PUBLISHER") "Altium Limited"))
      (libsource (lib "Miscellaneous Devices") (part "Res1"))
    )
    (comp (ref "R113")
      (value "R0603")
      (footprint "0603")
      (description "Resistor")
      (fields (field (name "ALTIUM_VALUE") "10R") (field (name "PUBLISHER") "Altium Limited"))
      (libsource (lib "Miscellaneous Devices") (part "Res1"))
    )
    (comp (ref "R114")
      (value "R0603")
      (footprint "0603")
      (description "Resistor")
      (fields (field (name "ALTIUM_VALUE") "10R") (field (name "PUBLISHER") "Altium Limited"))
      (libsource (lib "Miscellaneous Devices") (part "Res1"))
    )
    (comp (ref "R115")
      (value "R0603")
      (footprint "0603")
      (description "Resistor")
      (fields (field (name "ALTIUM_VALUE") "10R") (field (name "PUBLISHER") "Altium Limited"))
      (libsource (lib "Miscellaneous Devices") (part "Res1"))
    )
    (comp (ref "R116")
      (value "R0603")
      (footprint "0603")
      (description "Resistor")
      (fields (field (name "ALTIUM_VALUE") "10K") (field (name "PUBLISHER") "Altium Limited"))
      (libsource (lib "Miscellaneous Devices") (part "Res1"))
    )
    (comp (ref "R117")
      (value "R0603")
      (footprint "0603")
      (description "Resistor")
      (fields (field (name "ALTIUM_VALUE") "10K") (field (name "PUBLISHER") "Altium Limited"))
      (libsource (lib "Miscellaneous Devices") (part "Res1"))
    )
    (comp (ref "R118")
      (value "R0603")
      (footprint "0603")
      (description "Resistor")
      (fields (field (name "ALTIUM_VALUE") "10K") (field (name "PUBLISHER") "Altium Limited"))
      (libsource (lib "Miscellaneous Devices") (part "Res1"))
    )
    (comp (ref "R119")
      (value "R0603")
      (footprint "0603")
      (description "Resistor")
      (fields (field (name "ALTIUM_VALUE") "1K") (field (name "PUBLISHER") "Altium Limited"))
      (libsource (lib "Miscellaneous Devices") (part "Res1"))
    )
    (comp (ref "R120")
      (value "R2512")
      (footprint "R2512")
      (description "Resistor")
      (fields (field (name "ALTIUM_VALUE") "0.02R") (field (name "PUBLISHER") "Altium Limited"))
      (libsource (lib "Miscellaneous Devices") (part "Res1"))
    )
    (comp (ref "R121")
      (value "R2512")
      (footprint "R2512")
      (description "Resistor")
      (fields (field (name "ALTIUM_VALUE") "0.02R") (field (name "PUBLISHER") "Altium Limited"))
      (libsource (lib "Miscellaneous Devices") (part "Res1"))
    )
    (comp (ref "R122")
      (value "R0603")
      (footprint "0603")
      (description "Resistor")
      (fields (field (name "ALTIUM_VALUE") "10K") (field (name "PUBLISHER") "Altium Limited"))
      (libsource (lib "Miscellaneous Devices") (part "Res1"))
    )
    (comp (ref "R123")
      (value "R0603")
      (footprint "0603")
      (description "Resistor")
      (fields (field (name "ALTIUM_VALUE") "64.9K") (field (name "PUBLISHER") "Altium Limited"))
      (libsource (lib "Miscellaneous Devices") (part "Res1"))
    )
    (comp (ref "R124")
      (value "R0603")
      (footprint "0603")
      (description "Resistor")
      (fields (field (name "ALTIUM_VALUE") "64.9K") (field (name "PUBLISHER") "Altium Limited"))
      (libsource (lib "Miscellaneous Devices") (part "Res1"))
    )
    (comp (ref "R125")
      (value "R1206")
      (footprint "1206")
      (description "Resistor")
      (fields (field (name "ALTIUM_VALUE") "N/A") (field (name "PUBLISHER") "Altium Limited"))
      (libsource (lib "Miscellaneous Devices") (part "Res1"))
    )
    (comp (ref "R126")
      (value "R1206")
      (footprint "1206")
      (description "Resistor")
      (fields (field (name "ALTIUM_VALUE") "N/A") (field (name "PUBLISHER") "Altium Limited"))
      (libsource (lib "Miscellaneous Devices") (part "Res1"))
    )
    (comp (ref "R127")
      (value "R0603")
      (footprint "0603")
      (description "Resistor")
      (fields (field (name "ALTIUM_VALUE") "10K") (field (name "PUBLISHER") "Altium Limited"))
      (libsource (lib "Miscellaneous Devices") (part "Res1"))
    )
    (comp (ref "R128")
      (value "R0603")
      (footprint "0603")
      (description "Resistor")
      (fields (field (name "ALTIUM_VALUE") "10K") (field (name "PUBLISHER") "Altium Limited"))
      (libsource (lib "Miscellaneous Devices") (part "Res1"))
    )
    (comp (ref "R129")
      (value "R0603")
      (footprint "0603")
      (description "Resistor")
      (fields (field (name "ALTIUM_VALUE") "10K") (field (name "PUBLISHER") "Altium Limited"))
      (libsource (lib "Miscellaneous Devices") (part "Res1"))
    )
    (comp (ref "R130")
      (value "R0603")
      (footprint "0603")
      (description "Resistor")
      (fields (field (name "ALTIUM_VALUE") "10K") (field (name "PUBLISHER") "Altium Limited"))
      (libsource (lib "Miscellaneous Devices") (part "Res1"))
    )
    (comp (ref "U1")
      (value "SO-14")
      (footprint "SO-14")
      (description "Quadruple 2-Input Positive-AND Gate")
      (fields (field (name "ALTIUM_VALUE") "NXP 74HCT08") (field (name "PUBLISHER") "Altium Limited"))
      (libsource (lib "TI Logic Gate 1") (part "SN74AHCT08N"))
    )
    (comp (ref "U2")
      (value "SO-14")
      (footprint "SO-14")
      (description "Hex Schmitt-Trigger Inverter")
      (fields (field (name "ALTIUM_VALUE") "NXP 74HCT14") (field (name "PUBLISHER") "Altium Limited"))
      (libsource (lib "TI Logic Gate 1") (part "SN74ACT14N"))
    )
    (comp (ref "U3")
      (value "SOP-20")
      (footprint "SOP-20")
      (fields (field (name "ALTIUM_VALUE") "SN74HC245NSR"))
      (libsource (lib "SCH") (part "74HC245"))
    )
    (comp (ref "U4")
      (value "XC6503D331")
      (footprint "SOT23-5")
      (libsource (lib "CYSchlib") (part "XC6503Dxxx"))
    )
    (comp (ref "U5")
      (value "SO-14")
      (footprint "SO-14")
      (description "Quadruple 2-Input Positive-AND Gate")
      (fields (field (name "ALTIUM_VALUE") "NXP 74HCT08") (field (name "PUBLISHER") "Altium Limited"))
      (libsource (lib "TI Logic Gate 1") (part "SN74AHCT08N"))
    )
    (comp (ref "U6")
      (value "LQFP48_N")
      (footprint "LQFP48_N")
      (description "STM32 ARM-based 32-bit MCU with 64 Kbytes Flash, 48-pin LQFP, Industrial Temperature")
      (fields (field (name "ALTIUM_VALUE") "STM32F030C8T6") (field (name "PUBLISHER") "*"))
      (libsource (lib "ST Microcontroller 32-Bit STM32 SCH") (part "STM32F103C8T6"))
    )
    (comp (ref "U7")
      (value "SO-14")
      (footprint "SO-14")
      (description "Quadruple 2-Input Positive-AND Gate")
      (fields (field (name "ALTIUM_VALUE") "NXP 74HCT08") (field (name "PUBLISHER") "Altium Limited"))
      (libsource (lib "TI Logic Gate 1") (part "SN74AHCT08N"))
    )
    (comp (ref "U8")
      (value "SOP-20")
      (footprint "SOP-20")
      (fields (field (name "ALTIUM_VALUE") "SN74HC245NSR"))
      (libsource (lib "") (part "74HC245_1"))
    )
    (comp (ref "U9")
      (value "SO-8")
      (footprint "SO-8")
      (fields (field (name "ALTIUM_VALUE") "LM393A"))
      (libsource (lib "CYSchlib") (part "OP"))
    )
    (comp (ref "U10")
      (value "SO-8")
      (footprint "SO-8")
      (fields (field (name "ALTIUM_VALUE") "LM393A"))
      (libsource (lib "CYSchlib") (part "OP"))
    )
    (comp (ref "X1")
      (value "8M")
      (footprint "HC-49SMD")
      (fields (field (name "ALTIUM_VALUE") "HC-49SMD"))
      (libsource (lib "CYSchlib") (part "XTAL"))
    )
  )
  (nets
    (net (code "1") (name "/ADC-H-IN") (class "Default")
      (node (ref "C25") (pin "1") (pinfunction "1_1") (pintype "passive"))
      (node (ref "R27") (pin "1") (pinfunction "1_1") (pintype "passive"))
      (node (ref "U10") (pin "3") (pinfunction "3_3") (pintype "passive"))
    )
    (net (code "2") (name "/ADC-HEAD") (class "Default")
      (node (ref "C53") (pin "1") (pinfunction "1_1") (pintype "passive"))
      (node (ref "R118") (pin "2") (pinfunction "2_2") (pintype "passive"))
      (node (ref "U6") (pin "19") (pinfunction "PB1_19") (pintype "bidirectional"))
    )
    (net (code "3") (name "/ADC-L") (class "Default")
      (node (ref "C61") (pin "1") (pinfunction "1_1") (pintype "passive"))
      (node (ref "R79") (pin "2") (pinfunction "2_2") (pintype "passive"))
      (node (ref "U6") (pin "10") (pinfunction "PA0-WKUP_10") (pintype "bidirectional"))
    )
    (net (code "4") (name "/ADC-L-IN") (class "Default")
      (node (ref "C51") (pin "1") (pinfunction "1_1") (pintype "passive"))
      (node (ref "R116") (pin "2") (pinfunction "2_2") (pintype "passive"))
      (node (ref "U9") (pin "3") (pinfunction "3_3") (pintype "passive"))
    )
    (net (code "5") (name "/ADC-R") (class "Default")
      (node (ref "C62") (pin "1") (pinfunction "1_1") (pintype "passive"))
      (node (ref "R81") (pin "1") (pinfunction "1_1") (pintype "passive"))
      (node (ref "U6") (pin "11") (pinfunction "PA1_11") (pintype "bidirectional"))
    )
    (net (code "6") (name "/ADC-R-IN") (class "Default")
      (node (ref "C52") (pin "1") (pinfunction "1_1") (pintype "passive"))
      (node (ref "R117") (pin "2") (pinfunction "2_2") (pintype "passive"))
      (node (ref "U9") (pin "5") (pinfunction "5_5") (pintype "passive"))
    )
    (net (code "7") (name "/ADC-W-IN") (class "Default")
      (node (ref "C44") (pin "1") (pinfunction "1_1") (pintype "passive"))
      (node (ref "R76") (pin "1") (pinfunction "1_1") (pintype "passive"))
      (node (ref "U10") (pin "5") (pinfunction "5_5") (pintype "passive"))
    )
    (net (code "8") (name "/ADC-WING") (class "Default")
      (node (ref "C54") (pin "1") (pinfunction "1_1") (pintype "passive"))
      (node (ref "R122") (pin "1") (pinfunction "1_1") (pintype "passive"))
      (node (ref "U6") (pin "18") (pinfunction "PB0_18") (pintype "bidirectional"))
    )
    (net (code "9") (name "/DIR-IO-1") (class "Default")
      (node (ref "R102") (pin "2") (pinfunction "2_2") (pintype "passive"))
      (node (ref "U1") (pin "4") (pinfunction "A_4") (pintype "input"))
      (node (ref "U2") (pin "1") (pinfunction "A_1") (pintype "input"))
      (node (ref "U6") (pin "29") (pinfunction "PA8_29") (pintype "bidirectional"))
    )
    (net (code "10") (name "/DIR-IO-2") (class "Default")
      (node (ref "R99") (pin "2") (pinfunction "2_2") (pintype "passive"))
      (node (ref "U1") (pin "12") (pinfunction "A_12") (pintype "input"))
      (node (ref "U2") (pin "3") (pinfunction "A_3") (pintype "input"))
      (node (ref "U6") (pin "39") (pinfunction "PB3_39") (pintype "bidirectional"))
    )
    (net (code "11") (name "/DIR-IO-3") (class "Default")
      (node (ref "R26") (pin "2") (pinfunction "2_2") (pintype "passive"))
      (node (ref "U2") (pin "5") (pinfunction "A_5") (pintype "input"))
      (node (ref "U5") (pin "1") (pinfunction "A_1") (pintype "input"))
      (node (ref "U6") (pin "20") (pinfunction "PB2_20") (pintype "bidirectional"))
    )
    (net (code "12") (name "/DIR-IO-4") (class "Default")
      (node (ref "R52") (pin "2") (pinfunction "2_2") (pintype "passive"))
      (node (ref "U2") (pin "9") (pinfunction "A_9") (pintype "input"))
      (node (ref "U5") (pin "12") (pinfunction "A_12") (pintype "input"))
      (node (ref "U6") (pin "21") (pinfunction "PB10_21") (pintype "bidirectional"))
    )
    (net (code "13") (name "/DIR-IO-5") (class "Default")
      (node (ref "R70") (pin "2") (pinfunction "2_2") (pintype "passive"))
      (node (ref "U2") (pin "11") (pinfunction "A_11") (pintype "input"))
      (node (ref "U6") (pin "22") (pinfunction "PB11_22") (pintype "bidirectional"))
      (node (ref "U7") (pin "1") (pinfunction "A_1") (pintype "input"))
    )
    (net (code "14") (name "/DIR1N") (class "Default")
      (node (ref "R98") (pin "1") (pinfunction "1_1") (pintype "passive"))
      (node (ref "U1") (pin "2") (pinfunction "B_2") (pintype "input"))
      (node (ref "U2") (pin "2") (pinfunction "Y_2") (pintype "output"))
    )
    (net (code "15") (name "/DIR2N") (class "Default")
      (node (ref "R100") (pin "1") (pinfunction "1_1") (pintype "passive"))
      (node (ref "U1") (pin "10") (pinfunction "B_10") (pintype "input"))
      (node (ref "U2") (pin "4") (pinfunction "Y_4") (pintype "output"))
    )
    (net (code "16") (name "/DIR3N") (class "Default")
      (node (ref "R25") (pin "1") (pinfunction "1_1") (pintype "passive"))
      (node (ref "U2") (pin "6") (pinfunction "Y_6") (pintype "output"))
      (node (ref "U5") (pin "5") (pinfunction "B_5") (pintype "input"))
    )
    (net (code "17") (name "/DIR4N") (class "Default")
      (node (ref "R51") (pin "1") (pinfunction "1_1") (pintype "passive"))
      (node (ref "U2") (pin "8") (pinfunction "Y_8") (pintype "output"))
      (node (ref "U5") (pin "10") (pinfunction "B_10") (pintype "input"))
    )
    (net (code "18") (name "/DIR5N") (class "Default")
      (node (ref "R69") (pin "1") (pinfunction "1_1") (pintype "passive"))
      (node (ref "U2") (pin "10") (pinfunction "Y_10") (pintype "output"))
      (node (ref "U7") (pin "5") (pinfunction "B_5") (pintype "input"))
    )
    (net (code "19") (name "/ENC-HEAD-A") (class "Default")
      (node (ref "U3") (pin "5") (pinfunction "A3_5") (pintype "passive"))
      (node (ref "U6") (pin "35") (pinfunction "PF6_35") (pintype "power_in"))
    )
    (net (code "20") (name "/ENC-HEAD-A1") (class "Default")
      (node (ref "C9") (pin "1") (pinfunction "1_1") (pintype "passive"))
      (node (ref "J2") (pin "5") (pinfunction "5_5") (pintype "passive"))
      (node (ref "R4") (pin "1") (pinfunction "1_1") (pintype "passive"))
      (node (ref "U3") (pin "15") (pinfunction "B3_15") (pintype "passive"))
    )
    (net (code "21") (name "/ENC-HEAD-B") (class "Default")
      (node (ref "U3") (pin "4") (pinfunction "A2_4") (pintype "passive"))
      (node (ref "U6") (pin "36") (pinfunction "PF7_36") (pintype "power_in"))
    )
    (net (code "22") (name "/ENC-HEAD-B1") (class "Default")
      (node (ref "C8") (pin "1") (pinfunction "1_1") (pintype "passive"))
      (node (ref "J2") (pin "4") (pinfunction "4_4") (pintype "passive"))
      (node (ref "R3") (pin "1") (pinfunction "1_1") (pintype "passive"))
      (node (ref "U3") (pin "16") (pinfunction "B2_16") (pintype "passive"))
    )
    (net (code "23") (name "/ENC-L-A") (class "Default")
      (node (ref "U6") (pin "33") (pinfunction "PA12_33") (pintype "bidirectional"))
      (node (ref "U8") (pin "5") (pinfunction "A3_5") (pintype "passive"))
    )
    (net (code "24") (name "/ENC-L-A-J") (class "Default")
      (node (ref "C33") (pin "1") (pinfunction "1_1") (pintype "passive"))
      (node (ref "J7") (pin "2") (pinfunction "2_2") (pintype "passive"))
      (node (ref "R37") (pin "1") (pinfunction "1_1") (pintype "passive"))
      (node (ref "U8") (pin "15") (pinfunction "B3_15") (pintype "passive"))
    )
    (net (code "25") (name "/ENC-L-B") (class "Default")
      (node (ref "U6") (pin "32") (pinfunction "PA11_32") (pintype "bidirectional"))
      (node (ref "U8") (pin "4") (pinfunction "A2_4") (pintype "passive"))
    )
    (net (code "26") (name "/ENC-L-B-J") (class "Default")
      (node (ref "C34") (pin "1") (pinfunction "1_1") (pintype "passive"))
      (node (ref "J7") (pin "3") (pinfunction "3_3") (pintype "passive"))
      (node (ref "R38") (pin "1") (pinfunction "1_1") (pintype "passive"))
      (node (ref "U8") (pin "16") (pinfunction "B2_16") (pintype "passive"))
    )
    (net (code "27") (name "/ENC-R-A") (class "Default")
      (node (ref "U6") (pin "31") (pinfunction "PA10_31") (pintype "bidirectional"))
      (node (ref "U8") (pin "3") (pinfunction "A1_3") (pintype "passive"))
    )
    (net (code "28") (name "/ENC-R-A-J") (class "Default")
      (node (ref "C36") (pin "1") (pinfunction "1_1") (pintype "passive"))
      (node (ref "J7") (pin "5") (pinfunction "5_5") (pintype "passive"))
      (node (ref "R40") (pin "1") (pinfunction "1_1") (pintype "passive"))
      (node (ref "U8") (pin "17") (pinfunction "B1_17") (pintype "passive"))
    )
    (net (code "29") (name "/ENC-R-B") (class "Default")
      (node (ref "U6") (pin "30") (pinfunction "PA9_30") (pintype "bidirectional"))
      (node (ref "U8") (pin "2") (pinfunction "A0_2") (pintype "passive"))
    )
    (net (code "30") (name "/ENC-R-B-J") (class "Default")
      (node (ref "C37") (pin "1") (pinfunction "1_1") (pintype "passive"))
      (node (ref "J7") (pin "6") (pinfunction "6_6") (pintype "passive"))
      (node (ref "R41") (pin "1") (pinfunction "1_1") (pintype "passive"))
      (node (ref "U8") (pin "18") (pinfunction "B0_18") (pintype "passive"))
    )
    (net (code "31") (name "/ENC-W-L") (class "Default")
      (node (ref "U3") (pin "7") (pinfunction "A5_7") (pintype "passive"))
      (node (ref "U6") (pin "40") (pinfunction "PB4_40") (pintype "bidirectional"))
    )
    (net (code "32") (name "/ENC-W-L1") (class "Default")
      (node (ref "C22") (pin "1") (pinfunction "1_1") (pintype "passive"))
      (node (ref "J3") (pin "3") (pinfunction "3_3") (pintype "passive"))
      (node (ref "R15") (pin "1") (pinfunction "1_1") (pintype "passive"))
      (node (ref "U3") (pin "13") (pinfunction "B5_13") (pintype "passive"))
    )
    (net (code "33") (name "/ENC-W-R") (class "Default")
      (node (ref "U3") (pin "9") (pinfunction "A7_9") (pintype "passive"))
      (node (ref "U6") (pin "41") (pinfunction "PB5_41") (pintype "bidirectional"))
    )
    (net (code "34") (name "/ENC-W-R1") (class "Default")
      (node (ref "C24") (pin "1") (pinfunction "1_1") (pintype "passive"))
      (node (ref "J4") (pin "3") (pinfunction "3_3") (pintype "passive"))
      (node (ref "R17") (pin "1") (pinfunction "1_1") (pintype "passive"))
      (node (ref "U3") (pin "11") (pinfunction "B7_11") (pintype "passive"))
    )
    (net (code "35") (name "/FAULT") (class "Default")
      (node (ref "D3") (pin "1") (pinfunction "A_1") (pintype "passive"))
      (node (ref "D4") (pin "1") (pinfunction "A_1") (pintype "passive"))
      (node (ref "Q25") (pin "3") (pinfunction "C_3") (pintype "passive"))
      (node (ref "R129") (pin "2") (pinfunction "2_2") (pintype "passive"))
      (node (ref "U6") (pin "4") (pinfunction "PC15-OSC32-OUT_4") (pintype "bidirectional"))
    )
    (net (code "36") (name "/HEAD_IO_L") (class "Default")
      (node (ref "U3") (pin "3") (pinfunction "A1_3") (pintype "passive"))
      (node (ref "U6") (pin "45") (pinfunction "PB8_45") (pintype "bidirectional"))
    )
    (net (code "37") (name "/HEAD_IO_L1") (class "Default")
      (node (ref "C7") (pin "1") (pinfunction "1_1") (pintype "passive"))
      (node (ref "J2") (pin "3") (pinfunction "3_3") (pintype "passive"))
      (node (ref "R2") (pin "1") (pinfunction "1_1") (pintype "passive"))
      (node (ref "U3") (pin "17") (pinfunction "B1_17") (pintype "passive"))
    )
    (net (code "38") (name "/HEAD_IO_R") (class "Default")
      (node (ref "U3") (pin "2") (pinfunction "A0_2") (pintype "passive"))
      (node (ref "U6") (pin "46") (pinfunction "PB9_46") (pintype "bidirectional"))
    )
    (net (code "39") (name "/HEAD_IO_R1") (class "Default")
      (node (ref "C6") (pin "1") (pinfunction "1_1") (pintype "passive"))
      (node (ref "J2") (pin "2") (pinfunction "2_2") (pintype "passive"))
      (node (ref "R1") (pin "1") (pinfunction "1_1") (pintype "passive"))
      (node (ref "U3") (pin "18") (pinfunction "B0_18") (pintype "passive"))
    )
    (net (code "40") (name "/MOT-H-A") (class "Default")
      (node (ref "C28") (pin "2") (pinfunction "2_2") (pintype "passive"))
      (node (ref "J5") (pin "1") (pinfunction "1_1") (pintype "passive"))
      (node (ref "Q1") (pin "5") (pinfunction "D_5") (pintype "passive"))
      (node (ref "R33") (pin "2") (pinfunction "2_2") (pintype "passive"))
    )
    (net (code "41") (name "/MOT-H-B") (class "Default")
      (node (ref "C28") (pin "1") (pinfunction "1_1") (pintype "passive"))
      (node (ref "J5") (pin "2") (pinfunction "2_2") (pintype "passive"))
      (node (ref "Q2") (pin "5") (pinfunction "D_5") (pintype "passive"))
      (node (ref "R33") (pin "1") (pinfunction "1_1") (pintype "passive"))
    )
    (net (code "42") (name "/MOT-L-A") (class "Default")
      (node (ref "C56") (pin "2") (pinfunction "2_2") (pintype "passive"))
      (node (ref "J8") (pin "1") (pinfunction "1_1") (pintype "passive"))
      (node (ref "Q13") (pin "3") (pinfunction "D_3") (pintype "passive"))
      (node (ref "Q18") (pin "3") (pinfunction "D_3") (pintype "passive"))
      (node (ref "R126") (pin "2") (pinfunction "2_2") (pintype "passive"))
    )
    (net (code "43") (name "/MOT-L-B") (class "Default")
      (node (ref "C56") (pin "1") (pinfunction "1_1") (pintype "passive"))
      (node (ref "J8") (pin "2") (pinfunction "2_2") (pintype "passive"))
      (node (ref "Q14") (pin "3") (pinfunction "D_3") (pintype "passive"))
      (node (ref "Q19") (pin "3") (pinfunction "D_3") (pintype "passive"))
      (node (ref "R126") (pin "1") (pinfunction "1_1") (pintype "passive"))
    )
    (net (code "44") (name "/MOT-R-A") (class "Default")
      (node (ref "C55") (pin "2") (pinfunction "2_2") (pintype "passive"))
      (node (ref "J8") (pin "3") (pinfunction "3_3") (pintype "passive"))
      (node (ref "Q16") (pin "3") (pinfunction "D_3") (pintype "passive"))
      (node (ref "Q20") (pin "3") (pinfunction "D_3") (pintype "passive"))
      (node (ref "R125") (pin "2") (pinfunction "2_2") (pintype "passive"))
    )
    (net (code "45") (name "/MOT-R-B") (class "Default")
      (node (ref "C55") (pin "1") (pinfunction "1_1") (pintype "passive"))
      (node (ref "J8") (pin "4") (pinfunction "4_4") (pintype "passive"))
      (node (ref "Q15") (pin "3") (pinfunction "D_3") (pintype "passive"))
      (node (ref "Q21") (pin "3") (pinfunction "D_3") (pintype "passive"))
      (node (ref "R125") (pin "1") (pinfunction "1_1") (pintype "passive"))
    )
    (net (code "46") (name "/MOT-STOP1") (class "Default")
      (node (ref "C32") (pin "1") (pinfunction "1_1") (pintype "passive"))
      (node (ref "J1") (pin "5") (pinfunction "5_5") (pintype "passive"))
      (node (ref "R36") (pin "2") (pinfunction "2_2") (pintype "passive"))
      (node (ref "U8") (pin "12") (pinfunction "B6_12") (pintype "passive"))
    )
    (net (code "47") (name "/MOT-W-LA") (class "Default")
      (node (ref "C42") (pin "2") (pinfunction "2_2") (pintype "passive"))
      (node (ref "J3") (pin "6") (pinfunction "6_6") (pintype "passive"))
      (node (ref "Q5") (pin "5") (pinfunction "D_5") (pintype "passive"))
      (node (ref "R57") (pin "2") (pinfunction "2_2") (pintype "passive"))
    )
    (net (code "48") (name "/MOT-W-LB") (class "Default")
      (node (ref "C42") (pin "1") (pinfunction "1_1") (pintype "passive"))
      (node (ref "J3") (pin "5") (pinfunction "5_5") (pintype "passive"))
      (node (ref "Q6") (pin "5") (pinfunction "D_5") (pintype "passive"))
      (node (ref "R57") (pin "1") (pinfunction "1_1") (pintype "passive"))
    )
    (net (code "49") (name "/MOT-W-RA") (class "Default")
      (node (ref "C45") (pin "2") (pinfunction "2_2") (pintype "passive"))
      (node (ref "J4") (pin "7") (pinfunction "7_7") (pintype "passive"))
      (node (ref "Q9") (pin "5") (pinfunction "D_5") (pintype "passive"))
      (node (ref "R75") (pin "2") (pinfunction "2_2") (pintype "passive"))
    )
    (net (code "50") (name "/MOT-W-RB") (class "Default")
      (node (ref "C45") (pin "1") (pinfunction "1_1") (pintype "passive"))
      (node (ref "J4") (pin "6") (pinfunction "6_6") (pintype "passive"))
      (node (ref "Q10") (pin "5") (pinfunction "D_5") (pintype "passive"))
      (node (ref "R75") (pin "1") (pinfunction "1_1") (pintype "passive"))
    )
    (net (code "51") (name "/PWM-1-A") (class "Default")
      (node (ref "R112") (pin "1") (pinfunction "1_1") (pintype "passive"))
      (node (ref "U1") (pin "3") (pinfunction "Y_3") (pintype "output"))
    )
    (net (code "52") (name "/PWM-1-B") (class "Default")
      (node (ref "R113") (pin "1") (pinfunction "1_1") (pintype "passive"))
      (node (ref "U1") (pin "6") (pinfunction "Y_6") (pintype "output"))
    )
    (net (code "53") (name "/PWM-2-A") (class "Default")
      (node (ref "R114") (pin "1") (pinfunction "1_1") (pintype "passive"))
      (node (ref "U1") (pin "8") (pinfunction "Y_8") (pintype "output"))
    )
    (net (code "54") (name "/PWM-2-B") (class "Default")
      (node (ref "R115") (pin "1") (pinfunction "1_1") (pintype "passive"))
      (node (ref "U1") (pin "11") (pinfunction "Y_11") (pintype "output"))
    )
    (net (code "55") (name "/PWM-3-A") (class "Default")
      (node (ref "R29") (pin "2") (pinfunction "2_2") (pintype "passive"))
      (node (ref "U5") (pin "6") (pinfunction "Y_6") (pintype "output"))
    )
    (net (code "56") (name "/PWM-3-B") (class "Default")
      (node (ref "R30") (pin "2") (pinfunction "2_2") (pintype "passive"))
      (node (ref "U5") (pin "3") (pinfunction "Y_3") (pintype "output"))
    )
    (net (code "57") (name "/PWM-4-A") (class "Default")
      (node (ref "R54") (pin "2") (pinfunction "2_2") (pintype "passive"))
      (node (ref "U5") (pin "8") (pinfunction "Y_8") (pintype "output"))
    )
    (net (code "58") (name "/PWM-4-B") (class "Default")
      (node (ref "R55") (pin "2") (pinfunction "2_2") (pintype "passive"))
      (node (ref "U5") (pin "11") (pinfunction "Y_11") (pintype "output"))
    )
    (net (code "59") (name "/PWM-5-A") (class "Default")
      (node (ref "R72") (pin "2") (pinfunction "2_2") (pintype "passive"))
      (node (ref "U7") (pin "6") (pinfunction "Y_6") (pintype "output"))
    )
    (net (code "60") (name "/PWM-5-B") (class "Default")
      (node (ref "R73") (pin "2") (pinfunction "2_2") (pintype "passive"))
      (node (ref "U7") (pin "3") (pinfunction "Y_3") (pintype "output"))
    )
    (net (code "61") (name "/PWM-IO-1") (class "Default")
      (node (ref "R8") (pin "1") (pinfunction "1_1") (pintype "passive"))
      (node (ref "U1") (pin "1") (pinfunction "A_1") (pintype "input"))
      (node (ref "U1") (pin "5") (pinfunction "B_5") (pintype "input"))
      (node (ref "U6") (pin "12") (pinfunction "PA2_12") (pintype "bidirectional"))
    )
    (net (code "62") (name "/PWM-IO-2") (class "Default")
      (node (ref "R11") (pin "1") (pinfunction "1_1") (pintype "passive"))
      (node (ref "U1") (pin "13") (pinfunction "B_13") (pintype "input"))
      (node (ref "U1") (pin "9") (pinfunction "A_9") (pintype "input"))
      (node (ref "U6") (pin "13") (pinfunction "PA3_13") (pintype "bidirectional"))
    )
    (net (code "63") (name "/PWM-IO-3") (class "Default")
      (node (ref "R13") (pin "1") (pinfunction "1_1") (pintype "passive"))
      (node (ref "U5") (pin "2") (pinfunction "B_2") (pintype "input"))
      (node (ref "U5") (pin "4") (pinfunction "A_4") (pintype "input"))
      (node (ref "U6") (pin "14") (pinfunction "PA4_14") (pintype "bidirectional"))
    )
    (net (code "64") (name "/PWM-IO-4") (class "Default")
      (node (ref "R20") (pin "1") (pinfunction "1_1") (pintype "passive"))
      (node (ref "U5") (pin "13") (pinfunction "B_13") (pintype "input"))
      (node (ref "U5") (pin "9") (pinfunction "A_9") (pintype "input"))
      (node (ref "U6") (pin "16") (pinfunction "PA6_16") (pintype "bidirectional"))
    )
    (net (code "65") (name "/PWM-IO-5") (class "Default")
      (node (ref "R24") (pin "1") (pinfunction "1_1") (pintype "passive"))
      (node (ref "U6") (pin "17") (pinfunction "PA7_17") (pintype "bidirectional"))
      (node (ref "U7") (pin "2") (pinfunction "B_2") (pintype "input"))
      (node (ref "U7") (pin "4") (pinfunction "A_4") (pintype "input"))
    )
    (net (code "66") (name "/SEN1") (class "Default")
      (node (ref "D2") (pin "1") (pinfunction "A_1") (pintype "passive"))
      (node (ref "R59") (pin "1") (pinfunction "1_1") (pintype "passive"))
      (node (ref "U6") (pin "27") (pinfunction "PB14_27") (pintype "bidirectional"))
    )
    (net (code "67") (name "/SEN2") (class "Default")
      (node (ref "D5") (pin "1") (pinfunction "A_1") (pintype "passive"))
      (node (ref "R93") (pin "1") (pinfunction "1_1") (pintype "passive"))
      (node (ref "U6") (pin "26") (pinfunction "PB13_26") (pintype "bidirectional"))
    )
    (net (code "68") (name "/SWCLK") (class "Default")
      (node (ref "J6") (pin "3") (pinfunction "3_3") (pintype "passive"))
      (node (ref "U6") (pin "37") (pinfunction "PA14/JTCK/SWCLK_37") (pintype "bidirectional"))
    )
    (net (code "69") (name "/SWDIO") (class "Default")
      (node (ref "J6") (pin "2") (pinfunction "2_2") (pintype "passive"))
      (node (ref "U6") (pin "34") (pinfunction "PA13/JTMS/SWDIO_34") (pintype "bidirectional"))
    )
    (net (code "70") (name "/UART1RX") (class "Default")
      (node (ref "R23") (pin "1") (pinfunction "1_1") (pintype "passive"))
      (node (ref "U6") (pin "43") (pinfunction "PB7_43") (pintype "bidirectional"))
    )
    (net (code "71") (name "/UART1RX-J") (class "Default")
      (node (ref "D1") (pin "2") (pinfunction "2_2") (pintype "passive"))
      (node (ref "J1") (pin "6") (pinfunction "6_6") (pintype "passive"))
      (node (ref "R23") (pin "2") (pinfunction "2_2") (pintype "passive"))
    )
    (net (code "72") (name "/UART1TX") (class "Default")
      (node (ref "R12") (pin "1") (pinfunction "1_1") (pintype "passive"))
      (node (ref "U6") (pin "42") (pinfunction "PB6_42") (pintype "bidirectional"))
    )
    (net (code "73") (name "/UART1TX-J") (class "Default")
      (node (ref "D1") (pin "1") (pinfunction "1_1") (pintype "passive"))
      (node (ref "J1") (pin "7") (pinfunction "7_7") (pintype "passive"))
      (node (ref "R12") (pin "2") (pinfunction "2_2") (pintype "passive"))
    )
    (net (code "74") (name "/WHEEL-Float-L") (class "Default")
      (node (ref "D4") (pin "2") (pinfunction "K_2") (pintype "passive"))
      (node (ref "U6") (pin "3") (pinfunction "PC14-OSC32-IN_3") (pintype "bidirectional"))
      (node (ref "U8") (pin "6") (pinfunction "A4_6") (pintype "passive"))
    )
    (net (code "75") (name "/WHEEL-Float-L1") (class "Default")
      (node (ref "C35") (pin "1") (pinfunction "1_1") (pintype "passive"))
      (node (ref "J7") (pin "4") (pinfunction "4_4") (pintype "passive"))
      (node (ref "R39") (pin "1") (pinfunction "1_1") (pintype "passive"))
      (node (ref "U8") (pin "14") (pinfunction "B4_14") (pintype "passive"))
    )
    (net (code "76") (name "/WHEEL-Float-R") (class "Default")
      (node (ref "D3") (pin "2") (pinfunction "K_2") (pintype "passive"))
      (node (ref "U6") (pin "2") (pinfunction "PC13-TAMPER-RTC_2") (pintype "bidirectional"))
      (node (ref "U8") (pin "7") (pinfunction "A5_7") (pintype "passive"))
    )
    (net (code "77") (name "/WHEEL-Float-R1") (class "Default")
      (node (ref "C38") (pin "1") (pinfunction "1_1") (pintype "passive"))
      (node (ref "J7") (pin "7") (pinfunction "7_7") (pintype "passive"))
      (node (ref "R42") (pin "1") (pinfunction "1_1") (pintype "passive"))
      (node (ref "U8") (pin "13") (pinfunction "B5_13") (pintype "passive"))
    )
    (net (code "78") (name "/W_IO_L") (class "Default")
      (node (ref "U3") (pin "6") (pinfunction "A4_6") (pintype "passive"))
      (node (ref "U6") (pin "28") (pinfunction "PB15_28") (pintype "bidirectional"))
    )
    (net (code "79") (name "/W_IO_L1") (class "Default")
      (node (ref "C21") (pin "1") (pinfunction "1_1") (pintype "passive"))
      (node (ref "J3") (pin "2") (pinfunction "2_2") (pintype "passive"))
      (node (ref "R14") (pin "1") (pinfunction "1_1") (pintype "passive"))
      (node (ref "U3") (pin "14") (pinfunction "B4_14") (pintype "passive"))
    )
    (net (code "80") (name "/W_IO_R") (class "Default")
      (node (ref "U3") (pin "8") (pinfunction "A6_8") (pintype "passive"))
      (node (ref "U6") (pin "38") (pinfunction "PA15/JTDI_38") (pintype "bidirectional"))
    )
    (net (code "81") (name "/W_IO_R1") (class "Default")
      (node (ref "C23") (pin "1") (pinfunction "1_1") (pintype "passive"))
      (node (ref "J4") (pin "2") (pinfunction "2_2") (pintype "passive"))
      (node (ref "R16") (pin "1") (pinfunction "1_1") (pintype "passive"))
      (node (ref "U3") (pin "12") (pinfunction "B6_12") (pintype "passive"))
    )
    (net (code "82") (name "3.3V") (class "Default")
      (node (ref "C13") (pin "1") (pinfunction "1_1") (pintype "passive"))
      (node (ref "C15") (pin "1") (pinfunction "1_1") (pintype "passive"))
      (node (ref "C16") (pin "2") (pinfunction "2_2") (pintype "passive"))
      (node (ref "C17") (pin "2") (pinfunction "2_2") (pintype "passive"))
      (node (ref "C19") (pin "1") (pinfunction "1_1") (pintype "passive"))
      (node (ref "C30") (pin "1") (pinfunction "1_1") (pintype "passive"))
      (node (ref "C31") (pin "1") (pinfunction "1_1") (pintype "passive"))
      (node (ref "C41") (pin "1") (pinfunction "1_1") (pintype "passive"))
      (node (ref "C46") (pin "1") (pinfunction "1_1") (pintype "passive"))
      (node (ref "C50") (pin "1") (pinfunction "1_1") (pintype "passive"))
      (node (ref "C57") (pin "1") (pinfunction "1_1") (pintype "passive"))
      (node (ref "C58") (pin "1") (pinfunction "1_1") (pintype "passive"))
      (node (ref "C60") (pin "1") (pinfunction "1_1") (pintype "passive"))
      (node (ref "D2") (pin "2") (pinfunction "K_2") (pintype "passive"))
      (node (ref "D5") (pin "2") (pinfunction "K_2") (pintype "passive"))
      (node (ref "J2") (pin "6") (pinfunction "6_6") (pintype "passive"))
      (node (ref "J3") (pin "1") (pinfunction "1_1") (pintype "passive"))
      (node (ref "J4") (pin "1") (pinfunction "1_1") (pintype "passive"))
      (node (ref "J6") (pin "1") (pinfunction "1_1") (pintype "passive"))
      (node (ref "R1") (pin "2") (pinfunction "2_2") (pintype "passive"))
      (node (ref "R111") (pin "2") (pinfunction "2_2") (pintype "passive"))
      (node (ref "R119") (pin "2") (pinfunction "2_2") (pintype "passive"))
      (node (ref "R129") (pin "1") (pinfunction "1_1") (pintype "passive"))
      (node (ref "R14") (pin "2") (pinfunction "2_2") (pintype "passive"))
      (node (ref "R15") (pin "2") (pinfunction "2_2") (pintype "passive"))
      (node (ref "R16") (pin "2") (pinfunction "2_2") (pintype "passive"))
      (node (ref "R17") (pin "2") (pinfunction "2_2") (pintype "passive"))
      (node (ref "R2") (pin "2") (pinfunction "2_2") (pintype "passive"))
      (node (ref "R3") (pin "2") (pinfunction "2_2") (pintype "passive"))
      (node (ref "R35") (pin "2") (pinfunction "2_2") (pintype "passive"))
      (node (ref "R37") (pin "2") (pinfunction "2_2") (pintype "passive"))
      (node (ref "R38") (pin "2") (pinfunction "2_2") (pintype "passive"))
      (node (ref "R39") (pin "2") (pinfunction "2_2") (pintype "passive"))
      (node (ref "R4") (pin "2") (pinfunction "2_2") (pintype "passive"))
      (node (ref "R40") (pin "2") (pinfunction "2_2") (pintype "passive"))
      (node (ref "R41") (pin "2") (pinfunction "2_2") (pintype "passive"))
      (node (ref "R42") (pin "2") (pinfunction "2_2") (pintype "passive"))
      (node (ref "R5") (pin "2") (pinfunction "2_2") (pintype "passive"))
      (node (ref "R64") (pin "2") (pinfunction "2_2") (pintype "passive"))
      (node (ref "R78") (pin "1") (pinfunction "1_1") (pintype "passive"))
      (node (ref "R80") (pin "1") (pinfunction "1_1") (pintype "passive"))
      (node (ref "U10") (pin "8") (pinfunction "VCC_8") (pintype "passive"))
      (node (ref "U3") (pin "20") (pinfunction "VCC_20") (pintype "passive"))
      (node (ref "U4") (pin "5") (pinfunction "OUT_5") (pintype "passive"))
      (node (ref "U6") (pin "1") (pinfunction "VDD_1") (pintype "power_in"))
      (node (ref "U6") (pin "24") (pinfunction "VDD-1_24") (pintype "power_in"))
      (node (ref "U6") (pin "48") (pinfunction "VDD-3_48") (pintype "power_in"))
      (node (ref "U6") (pin "9") (pinfunction "VDDA_9") (pintype "power_in"))
      (node (ref "U8") (pin "20") (pinfunction "VCC_20") (pintype "passive"))
      (node (ref "U9") (pin "8") (pinfunction "VCC_8") (pintype "passive"))
    )
    (net (code "83") (name "24V") (class "Default")
      (node (ref "C1") (pin "1") (pinfunction "1_1") (pintype "passive"))
      (node (ref "C3") (pin "1") (pinfunction "1_1") (pintype "passive"))
      (node (ref "C47") (pin "1") (pinfunction "1_1") (pintype "passive"))
      (node (ref "C48") (pin "1") (pinfunction "1_1") (pintype "passive"))
      (node (ref "F1") (pin "1") (pinfunction "1_1") (pintype "passive"))
      (node (ref "Q13") (pin "2") (pinfunction "S_2") (pintype "passive"))
      (node (ref "Q14") (pin "2") (pinfunction "S_2") (pintype "passive"))
      (node (ref "Q15") (pin "2") (pinfunction "S_2") (pintype "passive"))
      (node (ref "Q16") (pin "2") (pinfunction "S_2") (pintype "passive"))
      (node (ref "R86") (pin "2") (pinfunction "2_2") (pintype "passive"))
      (node (ref "R87") (pin "2") (pinfunction "2_2") (pintype "passive"))
      (node (ref "R88") (pin "2") (pinfunction "2_2") (pintype "passive"))
      (node (ref "R89") (pin "2") (pinfunction "2_2") (pintype "passive"))
      (node (ref "R90") (pin "2") (pinfunction "2_2") (pintype "passive"))
      (node (ref "R91") (pin "2") (pinfunction "2_2") (pintype "passive"))
      (node (ref "R92") (pin "2") (pinfunction "2_2") (pintype "passive"))
    )
    (net (code "84") (name "GND") (class "Default")
      (node (ref "C1") (pin "2") (pinfunction "2_2") (pintype "passive"))
      (node (ref "C10") (pin "2") (pinfunction "2_2") (pintype "passive"))
      (node (ref "C11") (pin "1") (pinfunction "1_1") (pintype "passive"))
      (node (ref "C12") (pin "1") (pinfunction "1_1") (pintype "passive"))
      (node (ref "C13") (pin "2") (pinfunction "2_2") (pintype "passive"))
      (node (ref "C14") (pin "1") (pinfunction "1_1") (pintype "passive"))
      (node (ref "C15") (pin "2") (pinfunction "2_2") (pintype "passive"))
      (node (ref "C16") (pin "1") (pinfunction "1_1") (pintype "passive"))
      (node (ref "C17") (pin "1") (pinfunction "1_1") (pintype "passive"))
      (node (ref "C18") (pin "2") (pinfunction "2_2") (pintype "passive"))
      (node (ref "C19") (pin "2") (pinfunction "2_2") (pintype "passive"))
      (node (ref "C2") (pin "2") (pinfunction "2_2") (pintype "passive"))
      (node (ref "C20") (pin "1") (pinfunction "1_1") (pintype "passive"))
      (node (ref "C21") (pin "2") (pinfunction "2_2") (pintype "passive"))
      (node (ref "C22") (pin "2") (pinfunction "2_2") (pintype "passive"))
      (node (ref "C23") (pin "2") (pinfunction "2_2") (pintype "passive"))
      (node (ref "C24") (pin "2") (pinfunction "2_2") (pintype "passive"))
      (node (ref "C25") (pin "2") (pinfunction "2_2") (pintype "passive"))
      (node (ref "C26") (pin "1") (pinfunction "1_1") (pintype "passive"))
      (node (ref "C27") (pin "1") (pinfunction "1_1") (pintype "passive"))
      (node (ref "C29") (pin "1") (pinfunction "1_1") (pintype "passive"))
      (node (ref "C3") (pin "2") (pinfunction "2_2") (pintype "passive"))
      (node (ref "C30") (pin "2") (pinfunction "2_2") (pintype "passive"))
      (node (ref "C31") (pin "2") (pinfunction "2_2") (pintype "passive"))
      (node (ref "C32") (pin "2") (pinfunction "2_2") (pintype "passive"))
      (node (ref "C33") (pin "2") (pinfunction "2_2") (pintype "passive"))
      (node (ref "C34") (pin "2") (pinfunction "2_2") (pintype "passive"))
      (node (ref "C35") (pin "2") (pinfunction "2_2") (pintype "passive"))
      (node (ref "C36") (pin "2") (pinfunction "2_2") (pintype "passive"))
      (node (ref "C37") (pin "2") (pinfunction "2_2") (pintype "passive"))
      (node (ref "C38") (pin "2") (pinfunction "2_2") (pintype "passive"))
      (node (ref "C39") (pin "2") (pinfunction "2_2") (pintype "passive"))
      (node (ref "C4") (pin "2") (pinfunction "2_2") (pintype "passive"))
      (node (ref "C40") (pin "2") (pinfunction "2_2") (pintype "passive"))
      (node (ref "C41") (pin "2") (pinfunction "2_2") (pintype "passive"))
      (node (ref "C43") (pin "2") (pinfunction "2_2") (pintype "passive"))
      (node (ref "C44") (pin "2") (pinfunction "2_2") (pintype "passive"))
      (node (ref "C46") (pin "2") (pinfunction "2_2") (pintype "passive"))
      (node (ref "C47") (pin "2") (pinfunction "2_2") (pintype "passive"))
      (node (ref "C48") (pin "2") (pinfunction "2_2") (pintype "passive"))
      (node (ref "C49") (pin "2") (pinfunction "2_2") (pintype "passive"))
      (node (ref "C5") (pin "2") (pinfunction "2_2") (pintype "passive"))
      (node (ref "C50") (pin "2") (pinfunction "2_2") (pintype "passive"))
      (node (ref "C51") (pin "2") (pinfunction "2_2") (pintype "passive"))
      (node (ref "C52") (pin "2") (pinfunction "2_2") (pintype "passive"))
      (node (ref "C53") (pin "2") (pinfunction "2_2") (pintype "passive"))
      (node (ref "C54") (pin "2") (pinfunction "2_2") (pintype "passive"))
      (node (ref "C57") (pin "2") (pinfunction "2_2") (pintype "passive"))
      (node (ref "C58") (pin "2") (pinfunction "2_2") (pintype "passive"))
      (node (ref "C59") (pin "2") (pinfunction "2_2") (pintype "passive"))
      (node (ref "C6") (pin "2") (pinfunction "2_2") (pintype "passive"))
      (node (ref "C60") (pin "2") (pinfunction "2_2") (pintype "passive"))
      (node (ref "C61") (pin "2") (pinfunction "2_2") (pintype "passive"))
      (node (ref "C62") (pin "2") (pinfunction "2_2") (pintype "passive"))
      (node (ref "C7") (pin "2") (pinfunction "2_2") (pintype "passive"))
      (node (ref "C8") (pin "2") (pinfunction "2_2") (pintype "passive"))
      (node (ref "C9") (pin "2") (pinfunction "2_2") (pintype "passive"))
      (node (ref "D1") (pin "3") (pintype "passive"))
      (node (ref "J1") (pin "3") (pinfunction "3_3") (pintype "passive"))
      (node (ref "J1") (pin "4") (pinfunction "4_4") (pintype "passive"))
      (node (ref "J2") (pin "1") (pinfunction "1_1") (pintype "passive"))
      (node (ref "J3") (pin "4") (pinfunction "4_4") (pintype "passive"))
      (node (ref "J4") (pin "4") (pinfunction "4_4") (pintype "passive"))
      (node (ref "J6") (pin "4") (pinfunction "4_4") (pintype "passive"))
      (node (ref "J7") (pin "1") (pinfunction "1_1") (pintype "passive"))
      (node (ref "Q11") (pin "2") (pinfunction "E_2") (pintype "passive"))
      (node (ref "Q12") (pin "2") (pinfunction "E_2") (pintype "passive"))
      (node (ref "Q17") (pin "2") (pinfunction "E_2") (pintype "passive"))
      (node (ref "Q22") (pin "2") (pinfunction "E_2") (pintype "passive"))
      (node (ref "Q23") (pin "2") (pinfunction "E_2") (pintype "passive"))
      (node (ref "Q24") (pin "2") (pinfunction "E_2") (pintype "passive"))
      (node (ref "Q25") (pin "2") (pinfunction "E_2") (pintype "passive"))
      (node (ref "Q3") (pin "2") (pinfunction "E_2") (pintype "passive"))
      (node (ref "Q4") (pin "2") (pinfunction "E_2") (pintype "passive"))
      (node (ref "Q7") (pin "2") (pinfunction "E_2") (pintype "passive"))
      (node (ref "Q8") (pin "2") (pinfunction "E_2") (pintype "passive"))
      (node (ref "R101") (pin "1") (pinfunction "1_1") (pintype "passive"))
      (node (ref "R103") (pin "1") (pinfunction "1_1") (pintype "passive"))
      (node (ref "R106") (pin "1") (pinfunction "1_1") (pintype "passive"))
      (node (ref "R109") (pin "1") (pinfunction "1_1") (pintype "passive"))
      (node (ref "R11") (pin "2") (pinfunction "2_2") (pintype "passive"))
      (node (ref "R110") (pin "1") (pinfunction "1_1") (pintype "passive"))
      (node (ref "R120") (pin "2") (pinfunction "2_2") (pintype "passive"))
      (node (ref "R121") (pin "2") (pinfunction "2_2") (pintype "passive"))
      (node (ref "R127") (pin "1") (pinfunction "1_1") (pintype "passive"))
      (node (ref "R128") (pin "1") (pinfunction "1_1") (pintype "passive"))
      (node (ref "R13") (pin "2") (pinfunction "2_2") (pintype "passive"))
      (node (ref "R20") (pin "2") (pinfunction "2_2") (pintype "passive"))
      (node (ref "R24") (pin "2") (pinfunction "2_2") (pintype "passive"))
      (node (ref "R28") (pin "1") (pinfunction "1_1") (pintype "passive"))
      (node (ref "R31") (pin "2") (pinfunction "2_2") (pintype "passive"))
      (node (ref "R32") (pin "2") (pinfunction "2_2") (pintype "passive"))
      (node (ref "R34") (pin "1") (pinfunction "1_1") (pintype "passive"))
      (node (ref "R36") (pin "1") (pinfunction "1_1") (pintype "passive"))
      (node (ref "R5") (pin "1") (pinfunction "1_1") (pintype "passive"))
      (node (ref "R53") (pin "1") (pinfunction "1_1") (pintype "passive"))
      (node (ref "R56") (pin "1") (pinfunction "1_1") (pintype "passive"))
      (node (ref "R6") (pin "1") (pinfunction "1_1") (pintype "passive"))
      (node (ref "R62") (pin "1") (pinfunction "1_1") (pintype "passive"))
      (node (ref "R7") (pin "1") (pinfunction "1_1") (pintype "passive"))
      (node (ref "R71") (pin "1") (pinfunction "1_1") (pintype "passive"))
      (node (ref "R74") (pin "1") (pinfunction "1_1") (pintype "passive"))
      (node (ref "R77") (pin "2") (pinfunction "2_2") (pintype "passive"))
      (node (ref "R8") (pin "2") (pinfunction "2_2") (pintype "passive"))
      (node (ref "R84") (pin "2") (pinfunction "2_2") (pintype "passive"))
      (node (ref "R85") (pin "2") (pinfunction "2_2") (pintype "passive"))
      (node (ref "R86") (pin "1") (pinfunction "1_1") (pintype "passive"))
      (node (ref "R87") (pin "1") (pinfunction "1_1") (pintype "passive"))
      (node (ref "U1") (pin "7") (pinfunction "GND_7") (pintype "power_in"))
      (node (ref "U10") (pin "4") (pinfunction "GND_4") (pintype "passive"))
      (node (ref "U2") (pin "7") (pinfunction "GND_7") (pintype "power_in"))
      (node (ref "U3") (pin "1") (pinfunction "DIR_1") (pintype "passive"))
      (node (ref "U3") (pin "10") (pinfunction "GND_10") (pintype "passive"))
      (node (ref "U3") (pin "19") (pinfunction "~{OE}_19") (pintype "passive"))
      (node (ref "U4") (pin "2") (pinfunction "GND_2") (pintype "passive"))
      (node (ref "U5") (pin "7") (pinfunction "GND_7") (pintype "power_in"))
      (node (ref "U6") (pin "23") (pinfunction "VSS-1_23") (pintype "power_in"))
      (node (ref "U6") (pin "47") (pinfunction "VSS-3_47") (pintype "power_in"))
      (node (ref "U6") (pin "8") (pinfunction "VSSA_8") (pintype "power_in"))
      (node (ref "U7") (pin "7") (pinfunction "GND_7") (pintype "power_in"))
      (node (ref "U8") (pin "1") (pinfunction "DIR_1") (pintype "passive"))
      (node (ref "U8") (pin "10") (pinfunction "GND_10") (pintype "passive"))
      (node (ref "U8") (pin "11") (pinfunction "B7_11") (pintype "passive"))
      (node (ref "U8") (pin "19") (pinfunction "~{OE}_19") (pintype "passive"))
      (node (ref "U9") (pin "4") (pinfunction "GND_4") (pintype "passive"))
    )
    (net (code "85") (name "Net-(C43-Pad1)") (class "Default")
      (node (ref "C43") (pin "1") (pinfunction "1_1") (pintype "passive"))
      (node (ref "R58") (pin "1") (pinfunction "1_1") (pintype "passive"))
      (node (ref "R59") (pin "2") (pinfunction "2_2") (pintype "passive"))
      (node (ref "R62") (pin "2") (pinfunction "2_2") (pintype "passive"))
    )
    (net (code "86") (name "Net-(C49-Pad1)") (class "Default")
      (node (ref "C49") (pin "1") (pinfunction "1_1") (pintype "passive"))
      (node (ref "R101") (pin "2") (pinfunction "2_2") (pintype "passive"))
      (node (ref "R92") (pin "1") (pinfunction "1_1") (pintype "passive"))
      (node (ref "R93") (pin "2") (pinfunction "2_2") (pintype "passive"))
    )
    (net (code "87") (name "Net-(C59-Pad1)") (class "Default")
      (node (ref "C59") (pin "1") (pinfunction "1_1") (pintype "passive"))
      (node (ref "J7") (pin "8") (pinfunction "8_8") (pintype "passive"))
      (node (ref "R64") (pin "1") (pinfunction "1_1") (pintype "passive"))
      (node (ref "R65") (pin "1") (pinfunction "1_1") (pintype "passive"))
    )
    (net (code "88") (name "Net-(Q1-NG1)") (class "Default")
      (node (ref "Q1") (pin "2") (pinfunction "NG1_2") (pintype "passive"))
      (node (ref "R22") (pin "1") (pinfunction "1_1") (pintype "passive"))
      (node (ref "R29") (pin "1") (pinfunction "1_1") (pintype "passive"))
    )
    (net (code "89") (name "Net-(Q1-NS1)") (class "Default")
      (node (ref "Q1") (pin "1") (pinfunction "NS1_1") (pintype "passive"))
      (node (ref "Q2") (pin "1") (pinfunction "NS1_1") (pintype "passive"))
      (node (ref "R21") (pin "2") (pinfunction "2_2") (pintype "passive"))
      (node (ref "R22") (pin "2") (pinfunction "2_2") (pintype "passive"))
      (node (ref "R27") (pin "2") (pinfunction "2_2") (pintype "passive"))
      (node (ref "R32") (pin "1") (pinfunction "1_1") (pintype "passive"))
    )
    (net (code "90") (name "Net-(Q1-PG2)") (class "Default")
      (node (ref "Q1") (pin "4") (pinfunction "PG2_4") (pintype "passive"))
      (node (ref "R18") (pin "2") (pinfunction "2_2") (pintype "passive"))
      (node (ref "R9") (pin "1") (pinfunction "1_1") (pintype "passive"))
    )
    (net (code "91") (name "Net-(Q2-NG1)") (class "Default")
      (node (ref "Q2") (pin "2") (pinfunction "NG1_2") (pintype "passive"))
      (node (ref "R21") (pin "1") (pinfunction "1_1") (pintype "passive"))
      (node (ref "R30") (pin "1") (pinfunction "1_1") (pintype "passive"))
    )
    (net (code "92") (name "Net-(Q2-PG2)") (class "Default")
      (node (ref "Q2") (pin "4") (pinfunction "PG2_4") (pintype "passive"))
      (node (ref "R10") (pin "1") (pinfunction "1_1") (pintype "passive"))
      (node (ref "R19") (pin "2") (pinfunction "2_2") (pintype "passive"))
    )
    (net (code "93") (name "Net-(Q3-B)") (class "Default")
      (node (ref "Q3") (pin "1") (pinfunction "B_1") (pintype "passive"))
      (node (ref "R26") (pin "1") (pinfunction "1_1") (pintype "passive"))
      (node (ref "R28") (pin "2") (pinfunction "2_2") (pintype "passive"))
    )
    (net (code "94") (name "Net-(Q3-C)") (class "Default")
      (node (ref "Q3") (pin "3") (pinfunction "C_3") (pintype "passive"))
      (node (ref "R18") (pin "1") (pinfunction "1_1") (pintype "passive"))
    )
    (net (code "95") (name "Net-(Q4-B)") (class "Default")
      (node (ref "Q4") (pin "1") (pinfunction "B_1") (pintype "passive"))
      (node (ref "R25") (pin "2") (pinfunction "2_2") (pintype "passive"))
      (node (ref "R31") (pin "1") (pinfunction "1_1") (pintype "passive"))
    )
    (net (code "96") (name "Net-(Q4-C)") (class "Default")
      (node (ref "Q4") (pin "3") (pinfunction "C_3") (pintype "passive"))
      (node (ref "R19") (pin "1") (pinfunction "1_1") (pintype "passive"))
    )
    (net (code "97") (name "Net-(Q5-NG1)") (class "Default")
      (node (ref "Q5") (pin "2") (pinfunction "NG1_2") (pintype "passive"))
      (node (ref "R49") (pin "2") (pinfunction "2_2") (pintype "passive"))
      (node (ref "R54") (pin "1") (pinfunction "1_1") (pintype "passive"))
    )
    (net (code "98") (name "Net-(Q5-PG2)") (class "Default")
      (node (ref "Q5") (pin "4") (pinfunction "PG2_4") (pintype "passive"))
      (node (ref "R45") (pin "1") (pinfunction "1_1") (pintype "passive"))
      (node (ref "R47") (pin "2") (pinfunction "2_2") (pintype "passive"))
    )
    (net (code "99") (name "Net-(Q6-NG1)") (class "Default")
      (node (ref "Q6") (pin "2") (pinfunction "NG1_2") (pintype "passive"))
      (node (ref "R50") (pin "2") (pinfunction "2_2") (pintype "passive"))
      (node (ref "R55") (pin "1") (pinfunction "1_1") (pintype "passive"))
    )
    (net (code "100") (name "Net-(Q6-PG2)") (class "Default")
      (node (ref "Q6") (pin "4") (pinfunction "PG2_4") (pintype "passive"))
      (node (ref "R46") (pin "1") (pinfunction "1_1") (pintype "passive"))
      (node (ref "R48") (pin "2") (pinfunction "2_2") (pintype "passive"))
    )
    (net (code "101") (name "Net-(Q7-B)") (class "Default")
      (node (ref "Q7") (pin "1") (pinfunction "B_1") (pintype "passive"))
      (node (ref "R52") (pin "1") (pinfunction "1_1") (pintype "passive"))
      (node (ref "R53") (pin "2") (pinfunction "2_2") (pintype "passive"))
    )
    (net (code "102") (name "Net-(Q7-C)") (class "Default")
      (node (ref "Q7") (pin "3") (pinfunction "C_3") (pintype "passive"))
      (node (ref "R47") (pin "1") (pinfunction "1_1") (pintype "passive"))
    )
    (net (code "103") (name "Net-(Q8-B)") (class "Default")
      (node (ref "Q8") (pin "1") (pinfunction "B_1") (pintype "passive"))
      (node (ref "R51") (pin "2") (pinfunction "2_2") (pintype "passive"))
      (node (ref "R56") (pin "2") (pinfunction "2_2") (pintype "passive"))
    )
    (net (code "104") (name "Net-(Q8-C)") (class "Default")
      (node (ref "Q8") (pin "3") (pinfunction "C_3") (pintype "passive"))
      (node (ref "R48") (pin "1") (pinfunction "1_1") (pintype "passive"))
    )
    (net (code "105") (name "Net-(Q9-NG1)") (class "Default")
      (node (ref "Q9") (pin "2") (pinfunction "NG1_2") (pintype "passive"))
      (node (ref "R68") (pin "2") (pinfunction "2_2") (pintype "passive"))
      (node (ref "R72") (pin "1") (pinfunction "1_1") (pintype "passive"))
    )
    (net (code "106") (name "Net-(Q9-PG2)") (class "Default")
      (node (ref "Q9") (pin "4") (pinfunction "PG2_4") (pintype "passive"))
      (node (ref "R60") (pin "1") (pinfunction "1_1") (pintype "passive"))
      (node (ref "R63") (pin "2") (pinfunction "2_2") (pintype "passive"))
    )
    (net (code "107") (name "Net-(Q10-NG1)") (class "Default")
      (node (ref "Q10") (pin "2") (pinfunction "NG1_2") (pintype "passive"))
      (node (ref "R67") (pin "2") (pinfunction "2_2") (pintype "passive"))
      (node (ref "R73") (pin "1") (pinfunction "1_1") (pintype "passive"))
    )
    (net (code "108") (name "Net-(Q10-NS1)") (class "Default")
      (node (ref "Q10") (pin "1") (pinfunction "NS1_1") (pintype "passive"))
      (node (ref "Q5") (pin "1") (pinfunction "NS1_1") (pintype "passive"))
      (node (ref "Q6") (pin "1") (pinfunction "NS1_1") (pintype "passive"))
      (node (ref "Q9") (pin "1") (pinfunction "NS1_1") (pintype "passive"))
      (node (ref "R49") (pin "1") (pinfunction "1_1") (pintype "passive"))
      (node (ref "R50") (pin "1") (pinfunction "1_1") (pintype "passive"))
      (node (ref "R67") (pin "1") (pinfunction "1_1") (pintype "passive"))
      (node (ref "R68") (pin "1") (pinfunction "1_1") (pintype "passive"))
      (node (ref "R76") (pin "2") (pinfunction "2_2") (pintype "passive"))
      (node (ref "R77") (pin "1") (pinfunction "1_1") (pintype "passive"))
    )
    (net (code "109") (name "Net-(Q10-PG2)") (class "Default")
      (node (ref "Q10") (pin "4") (pinfunction "PG2_4") (pintype "passive"))
      (node (ref "R61") (pin "1") (pinfunction "1_1") (pintype "passive"))
      (node (ref "R66") (pin "2") (pinfunction "2_2") (pintype "passive"))
    )
    (net (code "110") (name "Net-(Q11-B)") (class "Default")
      (node (ref "Q11") (pin "1") (pinfunction "B_1") (pintype "passive"))
      (node (ref "R70") (pin "1") (pinfunction "1_1") (pintype "passive"))
      (node (ref "R71") (pin "2") (pinfunction "2_2") (pintype "passive"))
    )
    (net (code "111") (name "Net-(Q11-C)") (class "Default")
      (node (ref "Q11") (pin "3") (pinfunction "C_3") (pintype "passive"))
      (node (ref "R63") (pin "1") (pinfunction "1_1") (pintype "passive"))
    )
    (net (code "112") (name "Net-(Q12-B)") (class "Default")
      (node (ref "Q12") (pin "1") (pinfunction "B_1") (pintype "passive"))
      (node (ref "R69") (pin "2") (pinfunction "2_2") (pintype "passive"))
      (node (ref "R74") (pin "2") (pinfunction "2_2") (pintype "passive"))
    )
    (net (code "113") (name "Net-(Q12-C)") (class "Default")
      (node (ref "Q12") (pin "3") (pinfunction "C_3") (pintype "passive"))
      (node (ref "R66") (pin "1") (pinfunction "1_1") (pintype "passive"))
    )
    (net (code "114") (name "Net-(Q13-G)") (class "Default")
      (node (ref "Q13") (pin "1") (pinfunction "G_1") (pintype "passive"))
      (node (ref "R88") (pin "1") (pinfunction "1_1") (pintype "passive"))
      (node (ref "R94") (pin "2") (pinfunction "2_2") (pintype "passive"))
    )
    (net (code "115") (name "Net-(Q14-G)") (class "Default")
      (node (ref "Q14") (pin "1") (pinfunction "G_1") (pintype "passive"))
      (node (ref "R89") (pin "1") (pinfunction "1_1") (pintype "passive"))
      (node (ref "R95") (pin "2") (pinfunction "2_2") (pintype "passive"))
    )
    (net (code "116") (name "Net-(Q15-G)") (class "Default")
      (node (ref "Q15") (pin "1") (pinfunction "G_1") (pintype "passive"))
      (node (ref "R91") (pin "1") (pinfunction "1_1") (pintype "passive"))
      (node (ref "R97") (pin "2") (pinfunction "2_2") (pintype "passive"))
    )
    (net (code "117") (name "Net-(Q16-G)") (class "Default")
      (node (ref "Q16") (pin "1") (pinfunction "G_1") (pintype "passive"))
      (node (ref "R90") (pin "1") (pinfunction "1_1") (pintype "passive"))
      (node (ref "R96") (pin "2") (pinfunction "2_2") (pintype "passive"))
    )
    (net (code "118") (name "Net-(Q17-B)") (class "Default")
      (node (ref "Q17") (pin "1") (pinfunction "B_1") (pintype "passive"))
      (node (ref "R106") (pin "2") (pinfunction "2_2") (pintype "passive"))
      (node (ref "R99") (pin "1") (pinfunction "1_1") (pintype "passive"))
    )
    (net (code "119") (name "Net-(Q17-C)") (class "Default")
      (node (ref "Q17") (pin "3") (pinfunction "C_3") (pintype "passive"))
      (node (ref "R96") (pin "1") (pinfunction "1_1") (pintype "passive"))
    )
    (net (code "120") (name "Net-(Q18-G)") (class "Default")
      (node (ref "Q18") (pin "1") (pinfunction "G_1") (pintype "passive"))
      (node (ref "R104") (pin "1") (pinfunction "1_1") (pintype "passive"))
      (node (ref "R112") (pin "2") (pinfunction "2_2") (pintype "passive"))
    )
    (net (code "121") (name "Net-(Q18-S)") (class "Default")
      (node (ref "Q18") (pin "2") (pinfunction "S_2") (pintype "passive"))
      (node (ref "Q19") (pin "2") (pinfunction "S_2") (pintype "passive"))
      (node (ref "R104") (pin "2") (pinfunction "2_2") (pintype "passive"))
      (node (ref "R105") (pin "2") (pinfunction "2_2") (pintype "passive"))
      (node (ref "R116") (pin "1") (pinfunction "1_1") (pintype "passive"))
      (node (ref "R120") (pin "1") (pinfunction "1_1") (pintype "passive"))
    )
    (net (code "122") (name "Net-(Q19-G)") (class "Default")
      (node (ref "Q19") (pin "1") (pinfunction "G_1") (pintype "passive"))
      (node (ref "R105") (pin "1") (pinfunction "1_1") (pintype "passive"))
      (node (ref "R113") (pin "2") (pinfunction "2_2") (pintype "passive"))
    )
    (net (code "123") (name "Net-(Q20-G)") (class "Default")
      (node (ref "Q20") (pin "1") (pinfunction "G_1") (pintype "passive"))
      (node (ref "R107") (pin "1") (pinfunction "1_1") (pintype "passive"))
      (node (ref "R114") (pin "2") (pinfunction "2_2") (pintype "passive"))
    )
    (net (code "124") (name "Net-(Q20-S)") (class "Default")
      (node (ref "Q20") (pin "2") (pinfunction "S_2") (pintype "passive"))
      (node (ref "Q21") (pin "2") (pinfunction "S_2") (pintype "passive"))
      (node (ref "R107") (pin "2") (pinfunction "2_2") (pintype "passive"))
      (node (ref "R108") (pin "2") (pinfunction "2_2") (pintype "passive"))
      (node (ref "R117") (pin "1") (pinfunction "1_1") (pintype "passive"))
      (node (ref "R121") (pin "1") (pinfunction "1_1") (pintype "passive"))
    )
    (net (code "125") (name "Net-(Q21-G)") (class "Default")
      (node (ref "Q21") (pin "1") (pinfunction "G_1") (pintype "passive"))
      (node (ref "R108") (pin "1") (pinfunction "1_1") (pintype "passive"))
      (node (ref "R115") (pin "2") (pinfunction "2_2") (pintype "passive"))
    )
    (net (code "126") (name "Net-(Q22-B)") (class "Default")
      (node (ref "Q22") (pin "1") (pinfunction "B_1") (pintype "passive"))
      (node (ref "R102") (pin "1") (pinfunction "1_1") (pintype "passive"))
      (node (ref "R103") (pin "2") (pinfunction "2_2") (pintype "passive"))
    )
    (net (code "127") (name "Net-(Q22-C)") (class "Default")
      (node (ref "Q22") (pin "3") (pinfunction "C_3") (pintype "passive"))
      (node (ref "R94") (pin "1") (pinfunction "1_1") (pintype "passive"))
    )
    (net (code "128") (name "Net-(Q23-B)") (class "Default")
      (node (ref "Q23") (pin "1") (pinfunction "B_1") (pintype "passive"))
      (node (ref "R110") (pin "2") (pinfunction "2_2") (pintype "passive"))
      (node (ref "R98") (pin "2") (pinfunction "2_2") (pintype "passive"))
    )
    (net (code "129") (name "Net-(Q23-C)") (class "Default")
      (node (ref "Q23") (pin "3") (pinfunction "C_3") (pintype "passive"))
      (node (ref "R95") (pin "1") (pinfunction "1_1") (pintype "passive"))
    )
    (net (code "130") (name "Net-(Q24-B)") (class "Default")
      (node (ref "Q24") (pin "1") (pinfunction "B_1") (pintype "passive"))
      (node (ref "R100") (pin "2") (pinfunction "2_2") (pintype "passive"))
      (node (ref "R109") (pin "2") (pinfunction "2_2") (pintype "passive"))
    )
    (net (code "131") (name "Net-(Q24-C)") (class "Default")
      (node (ref "Q24") (pin "3") (pinfunction "C_3") (pintype "passive"))
      (node (ref "R97") (pin "1") (pinfunction "1_1") (pintype "passive"))
    )
    (net (code "132") (name "Net-(Q25-B)") (class "Default")
      (node (ref "Q25") (pin "1") (pinfunction "B_1") (pintype "passive"))
      (node (ref "R130") (pin "1") (pinfunction "1_1") (pintype "passive"))
    )
    (net (code "133") (name "Net-(R78-Pad2)") (class "Default")
      (node (ref "R78") (pin "2") (pinfunction "2_2") (pintype "passive"))
      (node (ref "R79") (pin "1") (pinfunction "1_1") (pintype "passive"))
      (node (ref "R82") (pin "1") (pinfunction "1_1") (pintype "passive"))
      (node (ref "U9") (pin "1") (pinfunction "1_1") (pintype "passive"))
    )
    (net (code "134") (name "Net-(R80-Pad2)") (class "Default")
      (node (ref "R80") (pin "2") (pinfunction "2_2") (pintype "passive"))
      (node (ref "R81") (pin "2") (pinfunction "2_2") (pintype "passive"))
      (node (ref "R83") (pin "1") (pinfunction "1_1") (pintype "passive"))
      (node (ref "U9") (pin "7") (pinfunction "7_7") (pintype "passive"))
    )
    (net (code "135") (name "Net-(R82-Pad2)") (class "Default")
      (node (ref "R82") (pin "2") (pinfunction "2_2") (pintype "passive"))
      (node (ref "R84") (pin "1") (pinfunction "1_1") (pintype "passive"))
      (node (ref "U9") (pin "2") (pinfunction "2_2") (pintype "passive"))
    )
    (net (code "136") (name "Net-(R83-Pad2)") (class "Default")
      (node (ref "R83") (pin "2") (pinfunction "2_2") (pintype "passive"))
      (node (ref "R85") (pin "1") (pinfunction "1_1") (pintype "passive"))
      (node (ref "U9") (pin "6") (pinfunction "6_6") (pintype "passive"))
    )
    (net (code "137") (name "Net-(R111-Pad1)") (class "Default")
      (node (ref "R111") (pin "1") (pinfunction "1_1") (pintype "passive"))
      (node (ref "R118") (pin "1") (pinfunction "1_1") (pintype "passive"))
      (node (ref "R123") (pin "2") (pinfunction "2_2") (pintype "passive"))
      (node (ref "U10") (pin "1") (pinfunction "1_1") (pintype "passive"))
    )
    (net (code "138") (name "Net-(R119-Pad1)") (class "Default")
      (node (ref "R119") (pin "1") (pinfunction "1_1") (pintype "passive"))
      (node (ref "R122") (pin "2") (pinfunction "2_2") (pintype "passive"))
      (node (ref "R124") (pin "2") (pinfunction "2_2") (pintype "passive"))
      (node (ref "U10") (pin "7") (pinfunction "7_7") (pintype "passive"))
    )
    (net (code "139") (name "Net-(R123-Pad1)") (class "Default")
      (node (ref "R123") (pin "1") (pinfunction "1_1") (pintype "passive"))
      (node (ref "R127") (pin "2") (pinfunction "2_2") (pintype "passive"))
      (node (ref "U10") (pin "2") (pinfunction "2_2") (pintype "passive"))
    )
    (net (code "140") (name "Net-(R124-Pad1)") (class "Default")
      (node (ref "R124") (pin "1") (pinfunction "1_1") (pintype "passive"))
      (node (ref "R128") (pin "2") (pinfunction "2_2") (pintype "passive"))
      (node (ref "U10") (pin "6") (pinfunction "6_6") (pintype "passive"))
    )
    (net (code "141") (name "Net-(U6-BOOT0)") (class "Default")
      (node (ref "R34") (pin "2") (pinfunction "2_2") (pintype "passive"))
      (node (ref "U6") (pin "44") (pinfunction "BOOT0_44") (pintype "input"))
    )
    (net (code "142") (name "Net-(U6-NRST)") (class "Default")
      (node (ref "C29") (pin "2") (pinfunction "2_2") (pintype "passive"))
      (node (ref "R35") (pin "1") (pinfunction "1_1") (pintype "passive"))
      (node (ref "U6") (pin "7") (pinfunction "NRST_7") (pintype "bidirectional"))
    )
    (net (code "143") (name "Net-(U6-OSC-IN{slash}PD0)") (class "Default")
      (node (ref "C26") (pin "2") (pinfunction "2_2") (pintype "passive"))
      (node (ref "U6") (pin "5") (pinfunction "OSC-IN/PD0_5") (pintype "input"))
      (node (ref "X1") (pin "2") (pinfunction "2_2") (pintype "passive"))
    )
    (net (code "144") (name "Net-(U6-OSC-OUT{slash}PD1)") (class "Default")
      (node (ref "C27") (pin "2") (pinfunction "2_2") (pintype "passive"))
      (node (ref "U6") (pin "6") (pinfunction "OSC-OUT/PD1_6") (pintype "output"))
      (node (ref "X1") (pin "1") (pinfunction "1_1") (pintype "passive"))
    )
    (net (code "145") (name "Net-(U8-A6)") (class "Default")
      (node (ref "R130") (pin "2") (pinfunction "2_2") (pintype "passive"))
      (node (ref "U8") (pin "8") (pinfunction "A6_8") (pintype "passive"))
    )
    (net (code "146") (name "VCC-5V") (class "Default")
      (node (ref "C10") (pin "1") (pinfunction "1_1") (pintype "passive"))
      (node (ref "C11") (pin "2") (pinfunction "2_2") (pintype "passive"))
      (node (ref "C12") (pin "2") (pinfunction "2_2") (pintype "passive"))
      (node (ref "C14") (pin "2") (pinfunction "2_2") (pintype "passive"))
      (node (ref "C20") (pin "2") (pinfunction "2_2") (pintype "passive"))
      (node (ref "C40") (pin "1") (pinfunction "1_1") (pintype "passive"))
      (node (ref "C5") (pin "1") (pinfunction "1_1") (pintype "passive"))
      (node (ref "J1") (pin "8") (pinfunction "8_8") (pintype "passive"))
      (node (ref "R65") (pin "2") (pinfunction "2_2") (pintype "passive"))
      (node (ref "U1") (pin "14") (pinfunction "VCC_14") (pintype "power_in"))
      (node (ref "U2") (pin "13") (pinfunction "A_13") (pintype "input"))
      (node (ref "U2") (pin "14") (pinfunction "VCC_14") (pintype "power_in"))
      (node (ref "U4") (pin "1") (pinfunction "VIN_1") (pintype "passive"))
      (node (ref "U4") (pin "3") (pinfunction "CE_3") (pintype "passive"))
      (node (ref "U5") (pin "14") (pinfunction "VCC_14") (pintype "power_in"))
      (node (ref "U7") (pin "10") (pinfunction "B_10") (pintype "input"))
      (node (ref "U7") (pin "12") (pinfunction "A_12") (pintype "input"))
      (node (ref "U7") (pin "13") (pinfunction "B_13") (pintype "input"))
      (node (ref "U7") (pin "14") (pinfunction "VCC_14") (pintype "power_in"))
      (node (ref "U7") (pin "9") (pinfunction "A_9") (pintype "input"))
    )
    (net (code "147") (name "VCC-22V") (class "Default")
      (node (ref "F2") (pin "2") (pinfunction "2_2") (pintype "passive"))
      (node (ref "J1") (pin "2") (pinfunction "2_2") (pintype "passive"))
    )
    (net (code "148") (name "VCC-22V-O") (class "Default")
      (node (ref "C18") (pin "1") (pinfunction "1_1") (pintype "passive"))
      (node (ref "C2") (pin "1") (pinfunction "1_1") (pintype "passive"))
      (node (ref "C39") (pin "1") (pinfunction "1_1") (pintype "passive"))
      (node (ref "C4") (pin "1") (pinfunction "1_1") (pintype "passive"))
      (node (ref "F2") (pin "1") (pinfunction "1_1") (pintype "passive"))
      (node (ref "Q1") (pin "3") (pinfunction "PS2_3") (pintype "passive"))
      (node (ref "Q10") (pin "3") (pinfunction "PS2_3") (pintype "passive"))
      (node (ref "Q2") (pin "3") (pinfunction "PS2_3") (pintype "passive"))
      (node (ref "Q5") (pin "3") (pinfunction "PS2_3") (pintype "passive"))
      (node (ref "Q6") (pin "3") (pinfunction "PS2_3") (pintype "passive"))
      (node (ref "Q9") (pin "3") (pinfunction "PS2_3") (pintype "passive"))
      (node (ref "R10") (pin "2") (pinfunction "2_2") (pintype "passive"))
      (node (ref "R45") (pin "2") (pinfunction "2_2") (pintype "passive"))
      (node (ref "R46") (pin "2") (pinfunction "2_2") (pintype "passive"))
      (node (ref "R58") (pin "2") (pinfunction "2_2") (pintype "passive"))
      (node (ref "R6") (pin "2") (pinfunction "2_2") (pintype "passive"))
      (node (ref "R60") (pin "2") (pinfunction "2_2") (pintype "passive"))
      (node (ref "R61") (pin "2") (pinfunction "2_2") (pintype "passive"))
      (node (ref "R7") (pin "2") (pinfunction "2_2") (pintype "passive"))
      (node (ref "R9") (pin "2") (pinfunction "2_2") (pintype "passive"))
    )
    (net (code "149") (name "VCC-24V") (class "Default")
      (node (ref "F1") (pin "2") (pinfunction "2_2") (pintype "passive"))
      (node (ref "J1") (pin "1") (pinfunction "1_1") (pintype "passive"))
    )
    (net (code "150") (name "unconnected-(J4-Pad5)") (class "Default")
      (node (ref "J4") (pin "5") (pinfunction "5_5") (pintype "passive"))
    )
    (net (code "151") (name "unconnected-(U2F-Y-Pad12)") (class "Default")
      (node (ref "U2") (pin "12") (pinfunction "Y_12") (pintype "output"))
    )
    (net (code "152") (name "unconnected-(U4-NC-Pad4)") (class "Default")
      (node (ref "U4") (pin "4") (pinfunction "NC_4") (pintype "passive"))
    )
    (net (code "153") (name "unconnected-(U6-PA5-Pad15)") (class "Default")
      (node (ref "U6") (pin "15") (pinfunction "PA5_15") (pintype "bidirectional"))
    )
    (net (code "154") (name "unconnected-(U6-PB12-Pad25)") (class "Default")
      (node (ref "U6") (pin "25") (pinfunction "PB12_25") (pintype "bidirectional"))
    )
    (net (code "155") (name "unconnected-(U7C-Y-Pad8)") (class "Default")
      (node (ref "U7") (pin "8") (pinfunction "Y_8") (pintype "output"))
    )
    (net (code "156") (name "unconnected-(U7D-Y-Pad11)") (class "Default")
      (node (ref "U7") (pin "11") (pinfunction "Y_11") (pintype "output"))
    )
    (net (code "157") (name "unconnected-(U8-A7-Pad9)") (class "Default")
      (node (ref "U8") (pin "9") (pinfunction "A7_9") (pintype "passive"))
    )
  )
)
